# ProPrj_E24_5_0.net
KiCad netlist of a schematic drawn in EasyEDA Pro
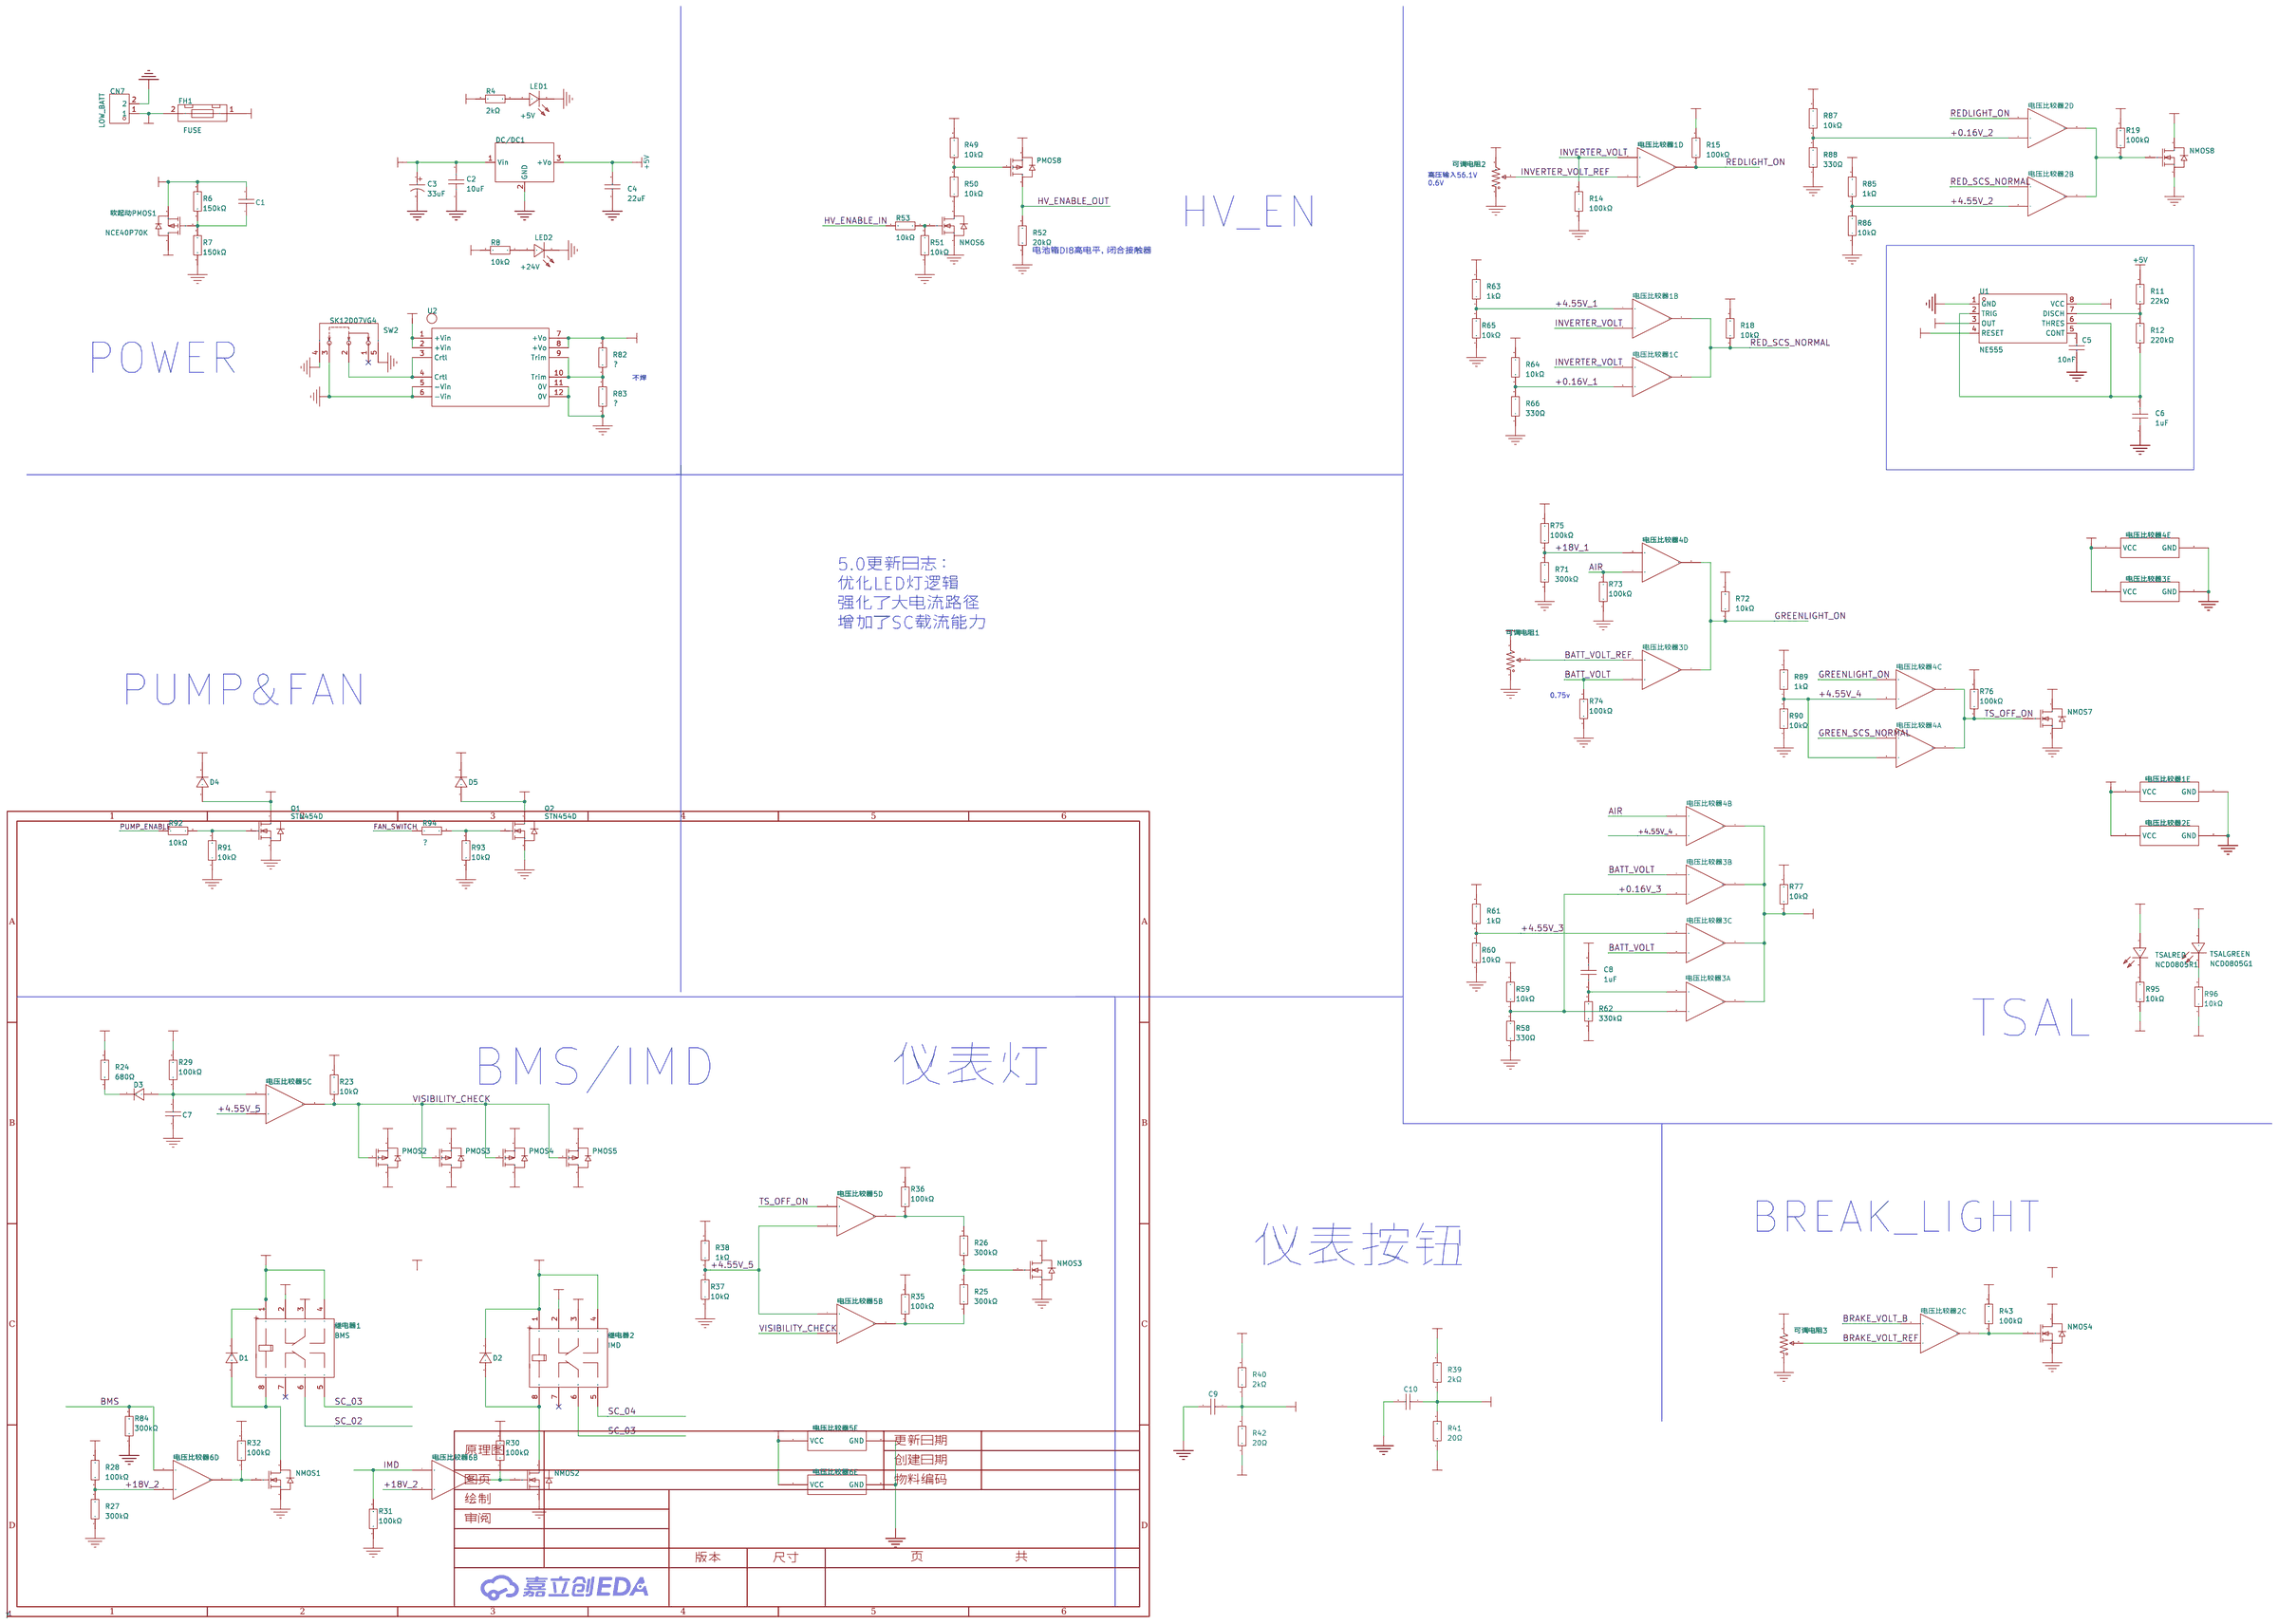
[diagram p0: P1]
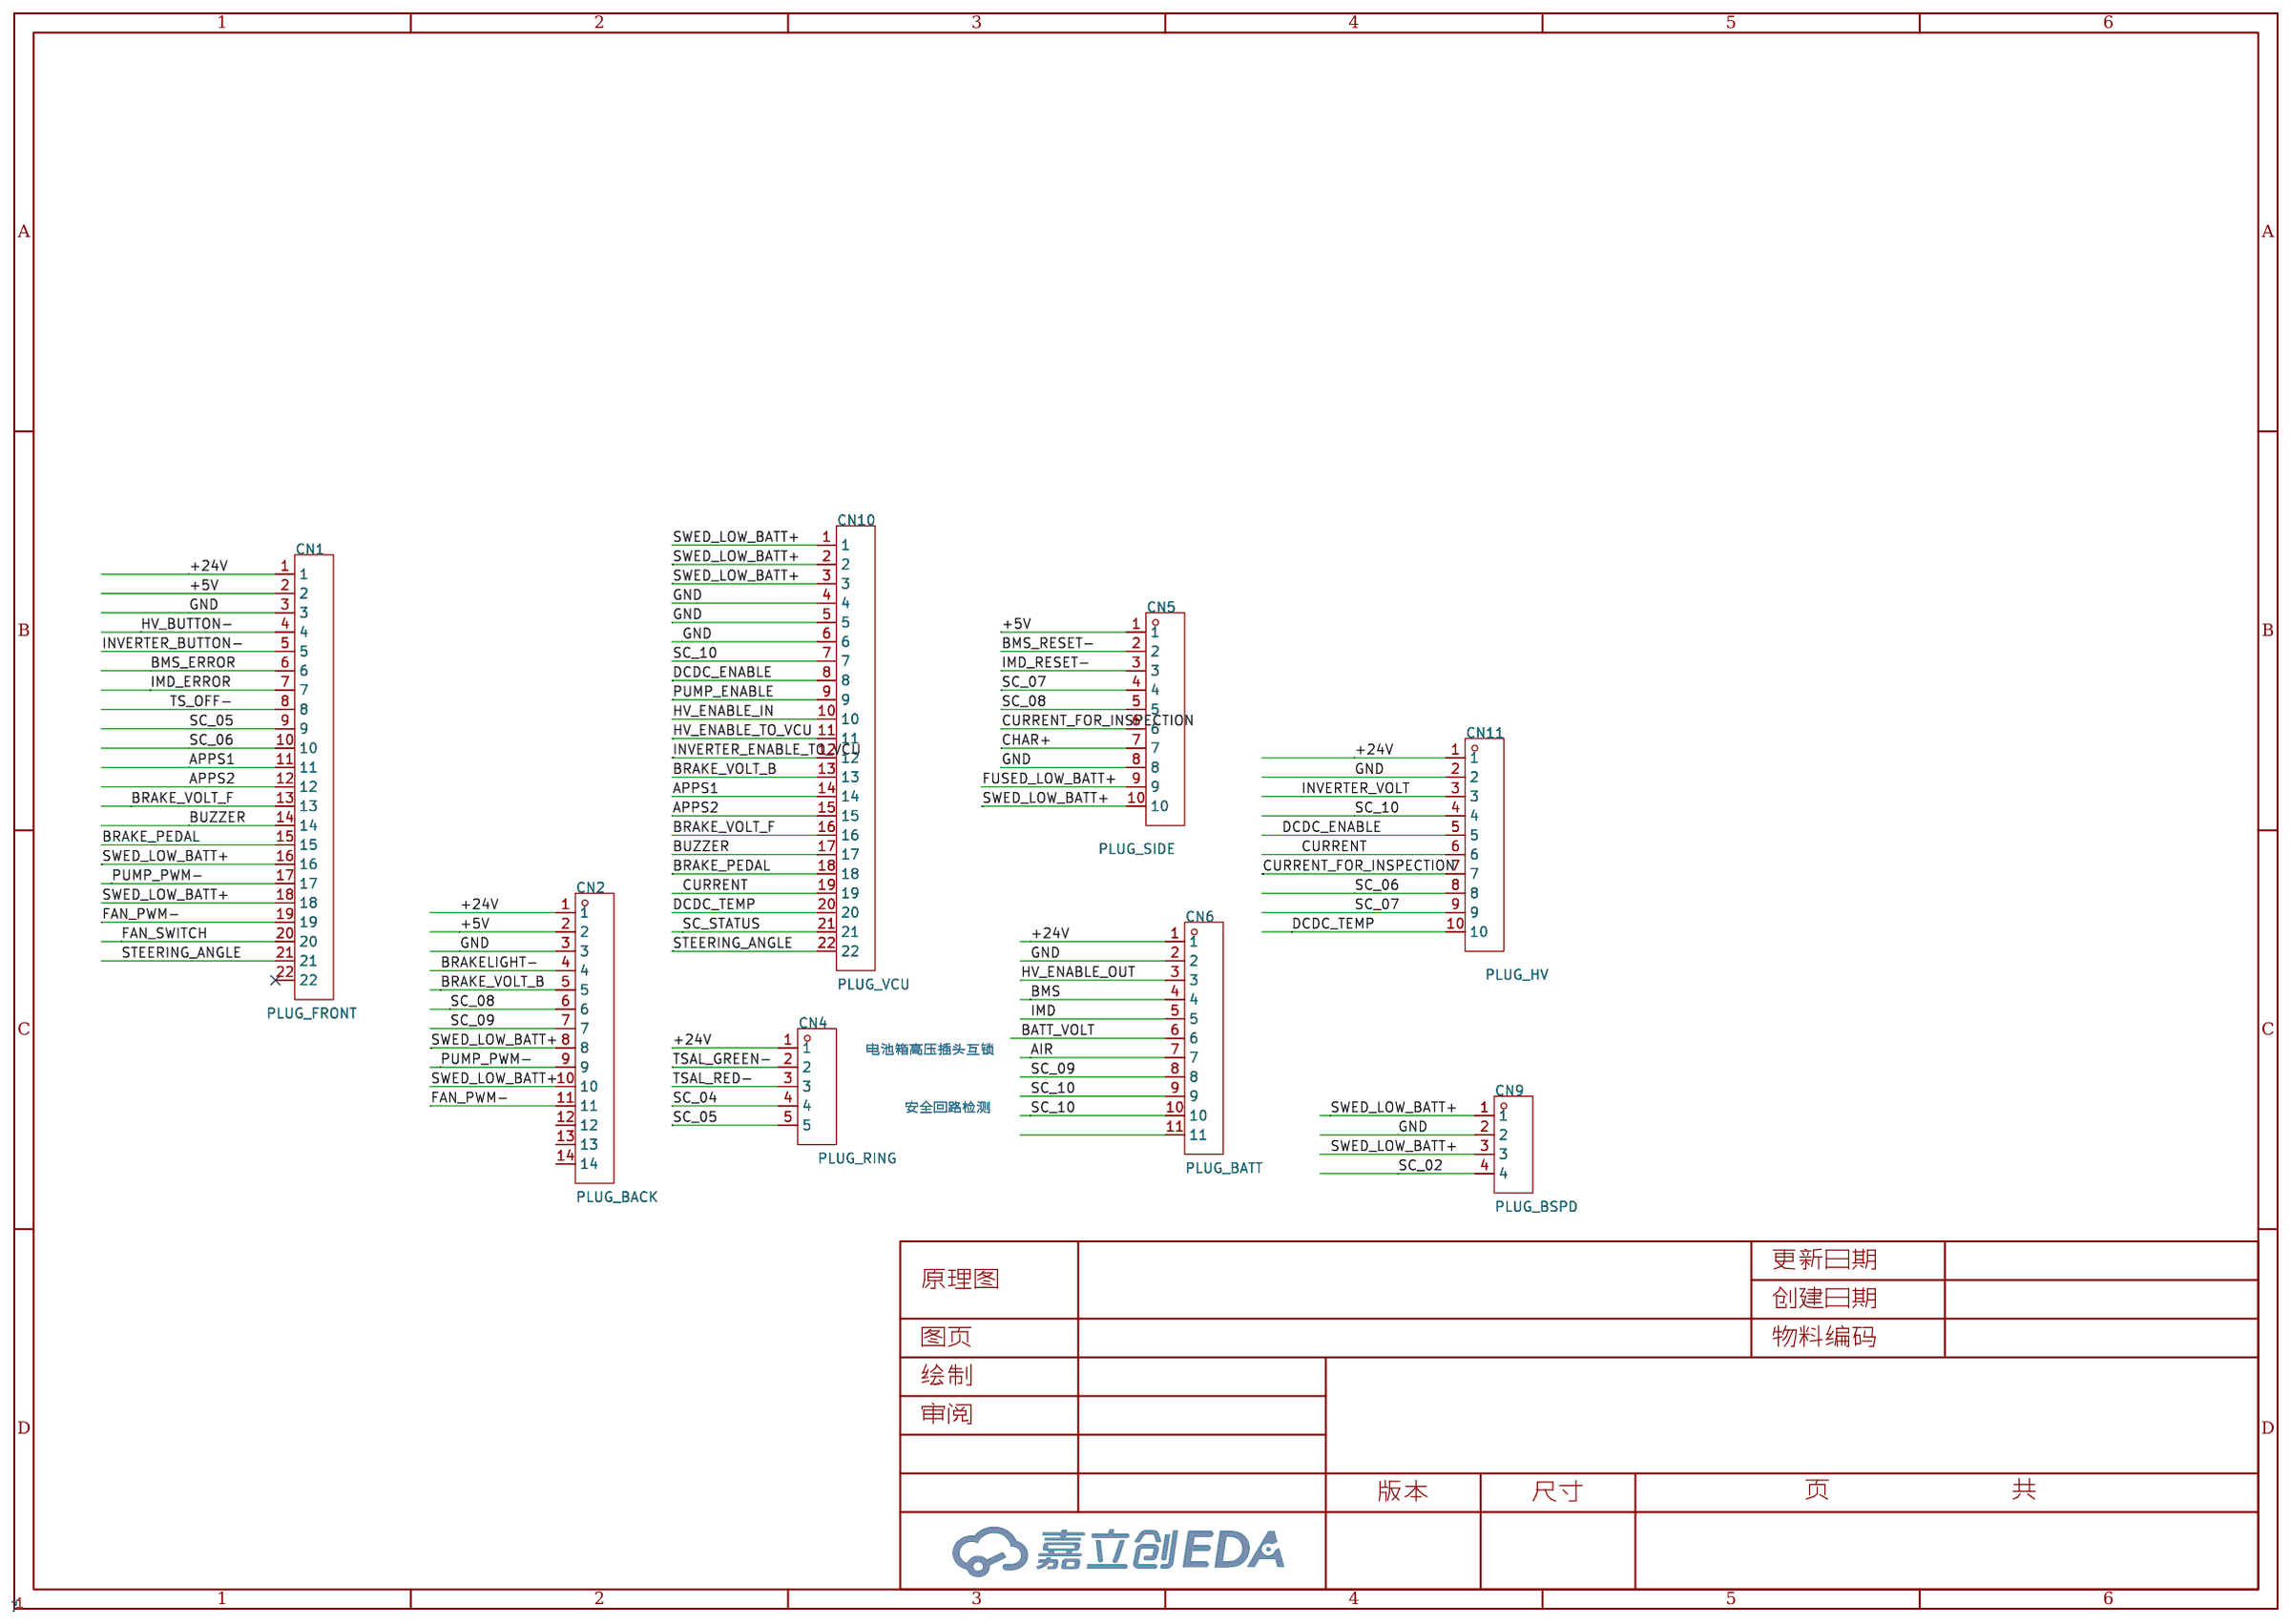
[diagram p1: P2]
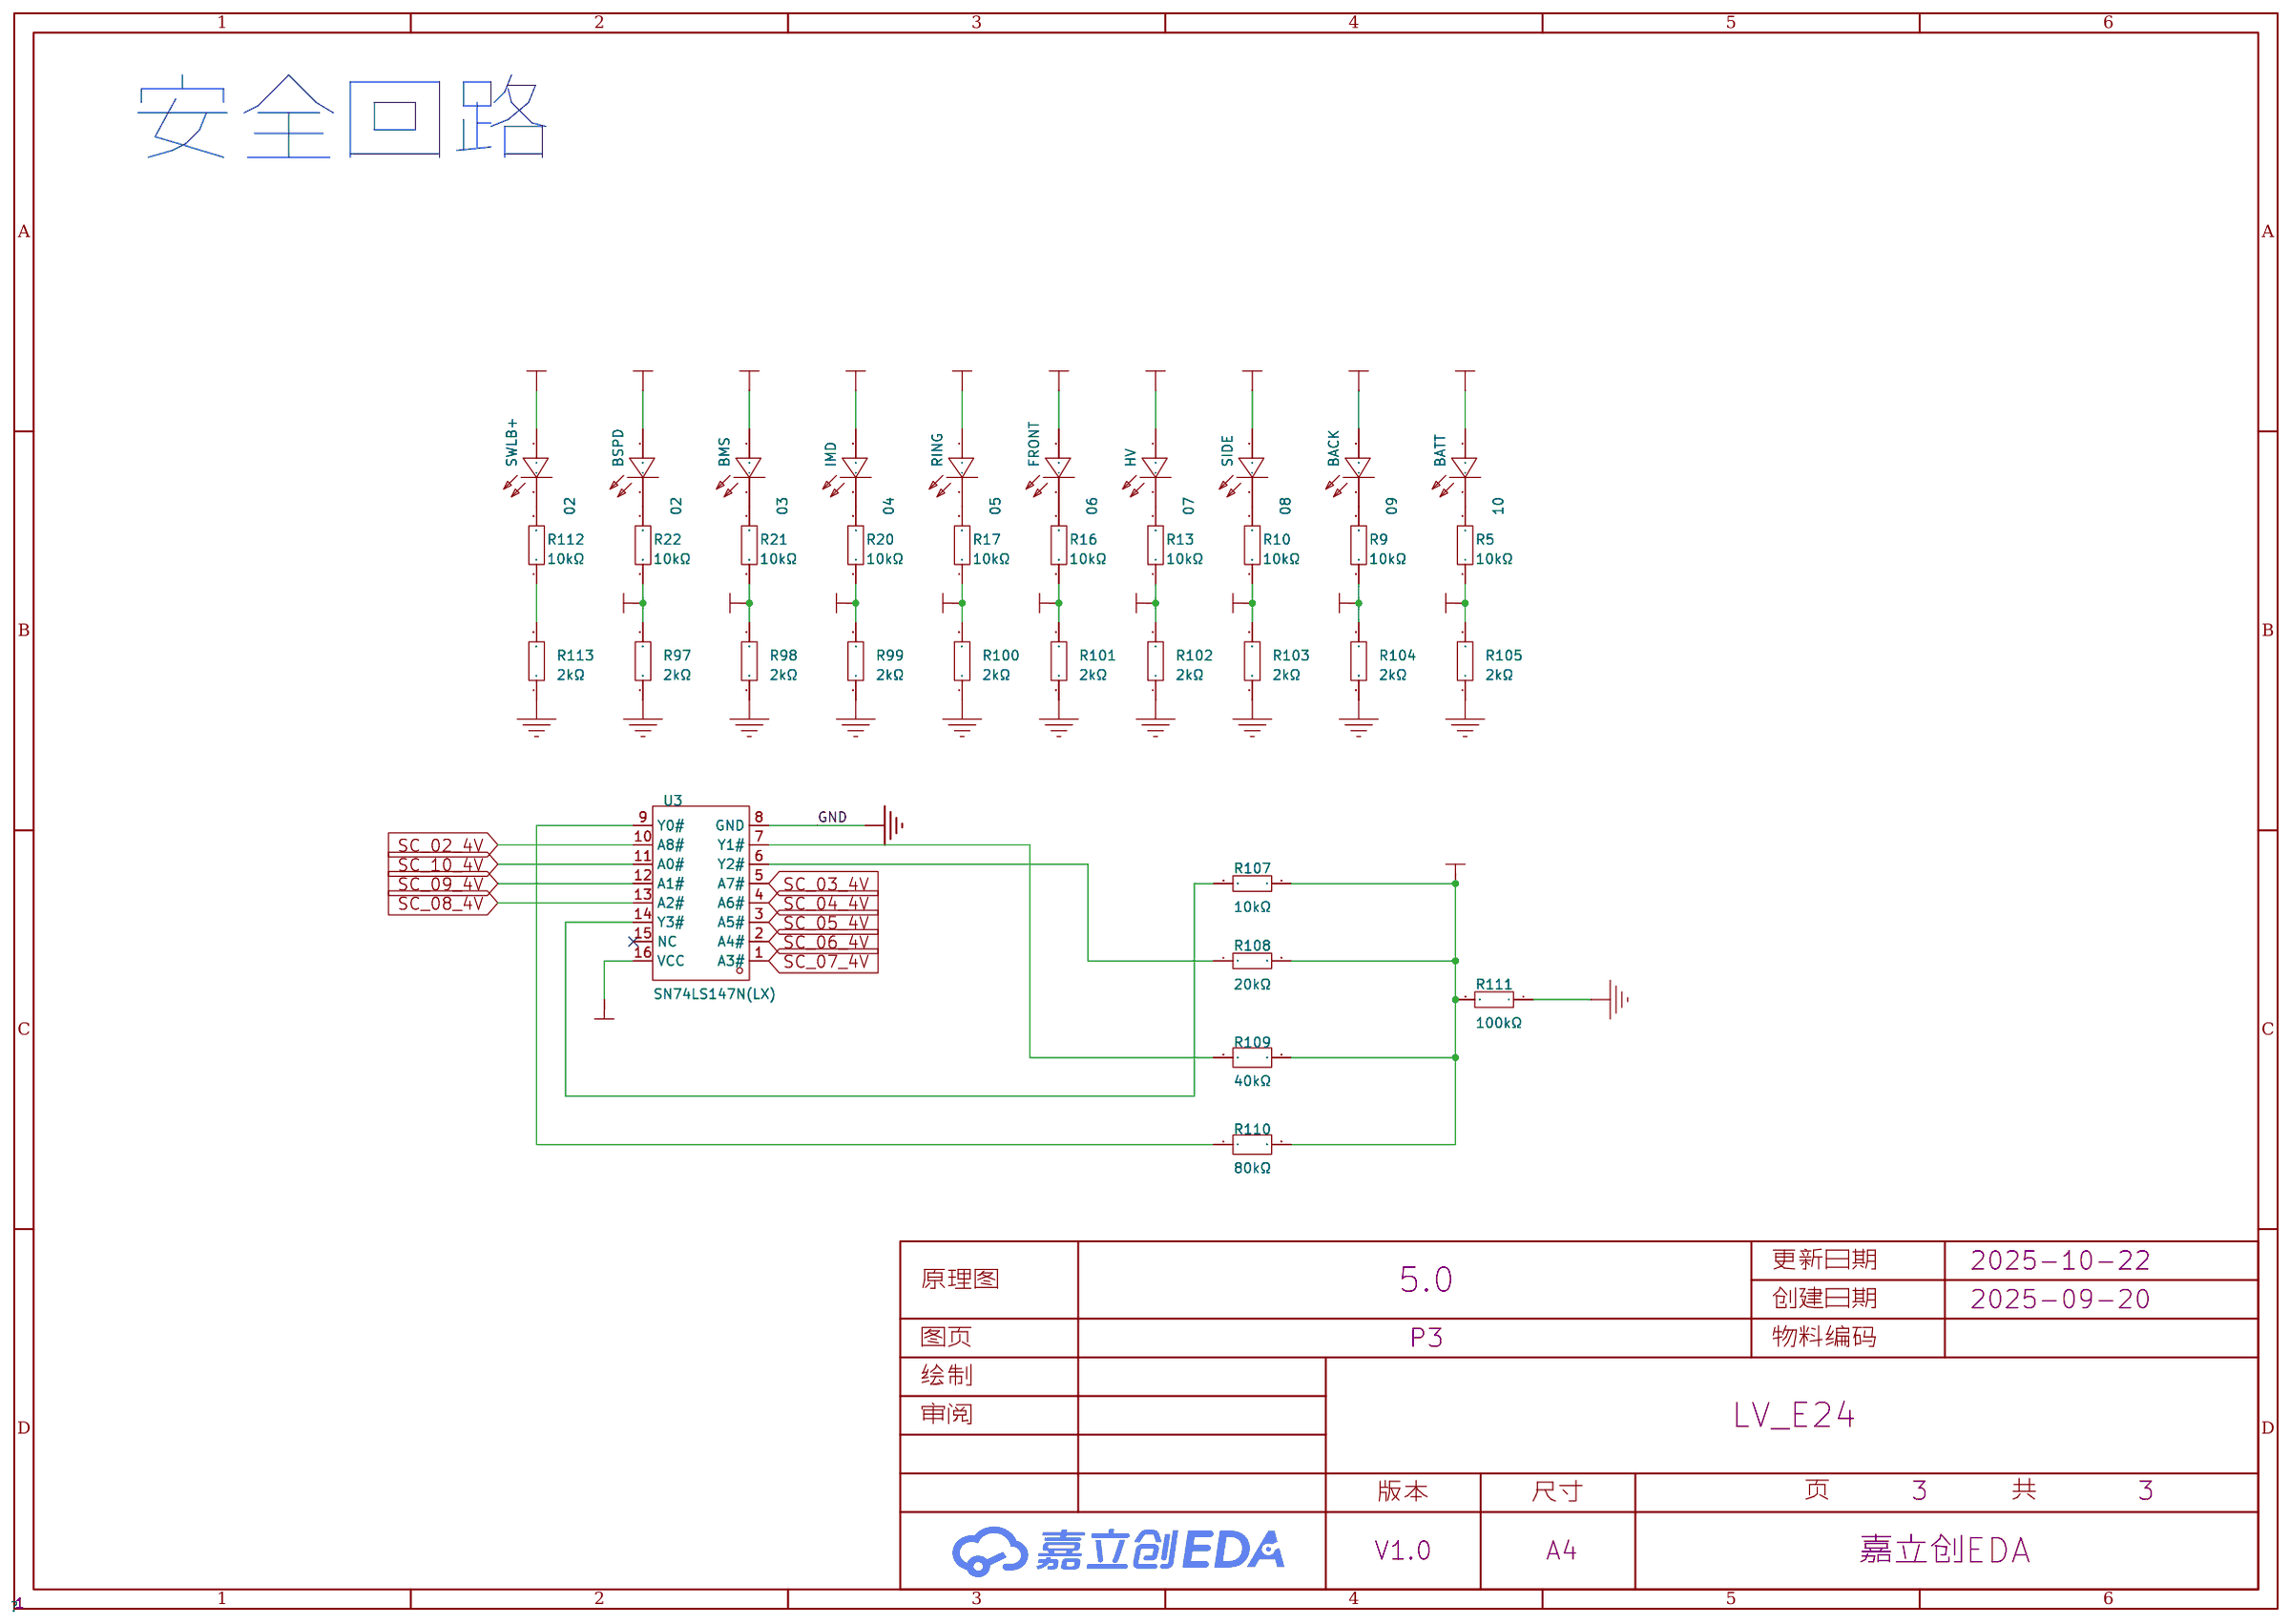
[diagram p2: P3]

(export (version "E")
  (design (tool "Eeschema 10.0.6"))
  (components
    (comp (ref "C1") (value "10uF") (libsource (lib "easyedapro") (part "C")))
    (comp (ref "C2")
      (value "10uF")
      (footprint "easyedapro:C1206")
      (description "容值:10uF;精度:±10%;额定电压:50V;材质(温度系数):X5R;")
      (fields
        (field (name "Manufacturer Part") "CS3216X5R106K500NRI")
        (field (name "Manufacturer") "SAMWHA(三和)")
      )
      (libsource (lib "easyedapro") (part "CS3216X5R106K500NRI"))
    )
    (comp (ref "C3")
      (value "33uF")
      (footprint "easyedapro:CAP-SMD_BD6.3-L6.6-W6.6-FD")
      (description "容值:33uF;精度:±20%;额定电压:35V;纹波电流:41mA@120Hz;等效串联电阻:-;")
      (fields (field (name "Manufacturer Part") "RVT1V330M0605") (field (name "Manufacturer") "ROQANG(容强)"))
      (libsource (lib "easyedapro") (part "RVT1V330M0605"))
    )
    (comp (ref "C4")
      (value "22uF")
      (footprint "easyedapro:C0805")
      (description "容值:22uF;精度:±20%;额定电压:10V;材质(温度系数):X5R;")
      (fields
        (field (name "Manufacturer Part") "CL21A226MPQNNNE")
        (field (name "Manufacturer") "SAMSUNG(三星)")
      )
      (libsource (lib "easyedapro") (part "CL21A226MPQNNNE"))
    )
    (comp (ref "C5")
      (value "10nF")
      (footprint "easyedapro:C0603")
      (description "容值:10nF;精度:±10%;额定电压:50V;材质(温度系数):X7R;")
      (fields
        (field (name "Manufacturer Part") "CC0603KRX7R9BB103")
        (field (name "Manufacturer") "YAGEO(国巨)")
      )
      (libsource (lib "easyedapro") (part "CC0603KRX7R9BB103"))
    )
    (comp (ref "C6")
      (value "1uF")
      (footprint "easyedapro:C0603")
      (description "容值:1uF;精度:±10%;额定电压:50V;材质(温度系数):X5R;")
      (fields
        (field (name "Manufacturer Part") "CL10A105KB8NNNC")
        (field (name "Manufacturer") "SAMSUNG(三星)")
      )
      (libsource (lib "easyedapro") (part "CL10A105KB8NNNC"))
    )
    (comp (ref "C7") (value "10uF") (libsource (lib "easyedapro") (part "C")))
    (comp (ref "C8")
      (value "1uF")
      (footprint "easyedapro:C0603")
      (description "容值:1uF;精度:±10%;额定电压:50V;材质(温度系数):X5R;")
      (fields
        (field (name "Manufacturer Part") "CL10A105KB8NNNC")
        (field (name "Manufacturer") "SAMSUNG(三星)")
      )
      (libsource (lib "easyedapro") (part "CL10A105KB8NNNC"))
    )
    (comp (ref "C9") (value "10uF") (libsource (lib "easyedapro") (part "C")))
    (comp (ref "C10") (value "10uF") (libsource (lib "easyedapro") (part "C")))
    (comp (ref "CN7")
      (value "LOW_BATT")
      (footprint "easyedapro:CONN-TH_2P-P3.81_DB2EVC-3.81-2P-BK")
      (fields
        (field (name "Manufacturer Part") "DB2EVC-3.81-2P-GN")
        (field (name "Manufacturer") "DORABO(地博电气)")
      )
      (libsource (lib "easyedapro") (part "DB2EVC-3.81-2P"))
    )
    (comp (ref "D1") (value "1N4148W") (libsource (lib "easyedapro") (part "1N4148W")))
    (comp (ref "D2") (value "1N4148W") (libsource (lib "easyedapro") (part "1N4148W")))
    (comp (ref "D3") (value "1N4148W") (libsource (lib "easyedapro") (part "1N4148W")))
    (comp (ref "D4") (value "SS54") (libsource (lib "easyedapro") (part "SS54")))
    (comp (ref "D5") (value "SS54") (libsource (lib "easyedapro") (part "SS54")))
    (comp (ref "DC/DC1") (value "K7805-2000R3") (libsource (lib "easyedapro") (part "K7805-2000R3")))
    (comp (ref "FH1")
      (value "FUSE")
      (footprint "easyedapro:FUSE-TH_XF-506P")
      (description "保险丝座类型:-;电路数:-;保险丝类型:-;")
      (fields (field (name "Manufacturer Part") "XF-506P") (field (name "Manufacturer") "XFCN(兴飞)"))
      (libsource (lib "easyedapro") (part "XF-506P"))
    )
    (comp (ref "LED1")
      (value "+5V")
      (footprint "easyedapro:LED0805-R-RD_BLUE")
      (fields (field (name "Manufacturer Part") "SZYY0805B") (field (name "Manufacturer") "yongyu(永裕光电)"))
      (libsource (lib "easyedapro") (part "SZYY0805B"))
    )
    (comp (ref "LED2")
      (value "+24V")
      (footprint "easyedapro:LED0805-R-RD_BLUE")
      (fields (field (name "Manufacturer Part") "SZYY0805B") (field (name "Manufacturer") "yongyu(永裕光电)"))
      (libsource (lib "easyedapro") (part "SZYY0805B"))
    )
    (comp (ref "NMOS1") (value "2N7002") (libsource (lib "easyedapro") (part "2N7002")))
    (comp (ref "NMOS2") (value "2N7002") (libsource (lib "easyedapro") (part "2N7002")))
    (comp (ref "NMOS3") (value "2N7002") (libsource (lib "easyedapro") (part "2N7002")))
    (comp (ref "NMOS4") (value "WST4040") (libsource (lib "easyedapro") (part "WST4040")))
    (comp (ref "NMOS6") (value "2N7002") (libsource (lib "easyedapro") (part "2N7002")))
    (comp (ref "NMOS7") (value "WST4040") (libsource (lib "easyedapro") (part "WST4040")))
    (comp (ref "NMOS8") (value "WST4040") (libsource (lib "easyedapro") (part "WST4040")))
    (comp (ref "PMOS2") (value "LBSS84LT1G") (libsource (lib "easyedapro") (part "LBSS84LT1G")))
    (comp (ref "PMOS3") (value "LBSS84LT1G") (libsource (lib "easyedapro") (part "LBSS84LT1G")))
    (comp (ref "PMOS4") (value "LBSS84LT1G") (libsource (lib "easyedapro") (part "LBSS84LT1G")))
    (comp (ref "PMOS5") (value "LBSS84LT1G") (libsource (lib "easyedapro") (part "LBSS84LT1G")))
    (comp (ref "PMOS8") (value "LBSS84LT1G") (libsource (lib "easyedapro") (part "LBSS84LT1G")))
    (comp (ref "Q1")
      (value "STN454D")
      (footprint "easyedapro:TO-252-2_L6.5-W6.1-P4.58-LS10.0-BR")
      (description "类型:1个N沟道;漏源电压(Vdss):40V;连续漏极电流(Id):10A;功率(Pd):50W;导通电阻(RDS(on)@Vgs,Id):-;阈值电压(Vgs(th)@Id):-;")
      (fields (field (name "Manufacturer") "STANSON(司坦森)"))
      (libsource (lib "easyedapro") (part "STN454D"))
    )
    (comp (ref "Q2")
      (value "STN454D")
      (footprint "easyedapro:TO-252-2_L6.5-W6.1-P4.58-LS10.0-BR")
      (description "类型:1个N沟道;漏源电压(Vdss):40V;连续漏极电流(Id):10A;功率(Pd):50W;导通电阻(RDS(on)@Vgs,Id):-;阈值电压(Vgs(th)@Id):-;")
      (fields (field (name "Manufacturer") "STANSON(司坦森)"))
      (libsource (lib "easyedapro") (part "STN454D"))
    )
    (comp (ref "R4")
      (value "2kΩ")
      (footprint "easyedapro:R0603")
      (description "电阻类型:厚膜电阻;阻值:2kΩ;精度:±1%;功率:100mW;最大工作电压:75V;温度系数:±100ppm/°C;")
      (fields
        (field (name "Manufacturer Part") "0603WAF2001T5E")
        (field (name "Manufacturer") "UNI-ROYAL(厚声)")
      )
      (libsource (lib "easyedapro") (part "0603WAF2001T5E"))
    )
    (comp (ref "R6")
      (value "150kΩ")
      (footprint "easyedapro:R0603")
      (description "电阻类型:厚膜电阻;阻值:150kΩ;精度:±1%;功率:100mW;最大工作电压:75V;温度系数:±100ppm/°C;")
      (fields
        (field (name "Manufacturer Part") "0603WAF1503T5E")
        (field (name "Manufacturer") "UNI-ROYAL(厚声)")
      )
      (libsource (lib "easyedapro") (part "0603WAF1503T5E"))
    )
    (comp (ref "R7")
      (value "150kΩ")
      (footprint "easyedapro:R0603")
      (description "电阻类型:厚膜电阻;阻值:150kΩ;精度:±1%;功率:100mW;最大工作电压:75V;温度系数:±100ppm/°C;")
      (fields
        (field (name "Manufacturer Part") "0603WAF1503T5E")
        (field (name "Manufacturer") "UNI-ROYAL(厚声)")
      )
      (libsource (lib "easyedapro") (part "0603WAF1503T5E"))
    )
    (comp (ref "R8")
      (value "10kΩ")
      (footprint "easyedapro:R0603")
      (description "电阻类型:厚膜电阻;阻值:10kΩ;精度:±1%;功率:100mW;最大工作电压:75V;温度系数:±100ppm/°C;")
      (fields
        (field (name "Manufacturer Part") "0603WAF1002T5E")
        (field (name "Manufacturer") "UNI-ROYAL(厚声)")
      )
      (libsource (lib "easyedapro") (part "0603WAF1002T5E"))
    )
    (comp (ref "R11")
      (value "22kΩ")
      (footprint "easyedapro:R0603")
      (description "电阻类型:厚膜电阻;阻值:22kΩ;精度:±1%;功率:100mW;最大工作电压:75V;温度系数:±100ppm/°C;")
      (fields
        (field (name "Manufacturer Part") "0603WAF2202T5E")
        (field (name "Manufacturer") "UNI-ROYAL(厚声)")
      )
      (libsource (lib "easyedapro") (part "0603WAF2202T5E"))
    )
    (comp (ref "R12")
      (value "220kΩ")
      (footprint "easyedapro:R0603")
      (description "电阻类型:厚膜电阻;阻值:220kΩ;精度:±1%;功率:100mW;最大工作电压:75V;温度系数:±100ppm/°C;")
      (fields
        (field (name "Manufacturer Part") "0603WAF2203T5E")
        (field (name "Manufacturer") "UNI-ROYAL(厚声)")
      )
      (libsource (lib "easyedapro") (part "0603WAF2203T5E"))
    )
    (comp (ref "R14")
      (value "100kΩ")
      (footprint "easyedapro:R0603")
      (description "电阻类型:厚膜电阻;阻值:100kΩ;精度:±1%;功率:100mW;最大工作电压:75V;温度系数:±100ppm/°C;")
      (fields
        (field (name "Manufacturer Part") "0603WAF1003T5E")
        (field (name "Manufacturer") "UNI-ROYAL(厚声)")
      )
      (libsource (lib "easyedapro") (part "0603WAF1003T5E"))
    )
    (comp (ref "R15")
      (value "100kΩ")
      (footprint "easyedapro:R0603")
      (description "电阻类型:厚膜电阻;阻值:100kΩ;精度:±1%;功率:100mW;最大工作电压:75V;温度系数:±100ppm/°C;")
      (fields
        (field (name "Manufacturer Part") "0603WAF1003T5E")
        (field (name "Manufacturer") "UNI-ROYAL(厚声)")
      )
      (libsource (lib "easyedapro") (part "0603WAF1003T5E"))
    )
    (comp (ref "R18")
      (value "10kΩ")
      (footprint "easyedapro:R0603")
      (description "电阻类型:厚膜电阻;阻值:10kΩ;精度:±1%;功率:100mW;最大工作电压:75V;温度系数:±100ppm/°C;")
      (fields
        (field (name "Manufacturer Part") "0603WAF1002T5E")
        (field (name "Manufacturer") "UNI-ROYAL(厚声)")
      )
      (libsource (lib "easyedapro") (part "0603WAF1002T5E"))
    )
    (comp (ref "R19")
      (value "100kΩ")
      (footprint "easyedapro:R0603")
      (description "电阻类型:厚膜电阻;阻值:100kΩ;精度:±1%;功率:100mW;最大工作电压:75V;温度系数:±100ppm/°C;")
      (fields
        (field (name "Manufacturer Part") "0603WAF1003T5E")
        (field (name "Manufacturer") "UNI-ROYAL(厚声)")
      )
      (libsource (lib "easyedapro") (part "0603WAF1003T5E"))
    )
    (comp (ref "R23")
      (value "10kΩ")
      (footprint "easyedapro:R0603")
      (description "电阻类型:厚膜电阻;阻值:10kΩ;精度:±1%;功率:100mW;最大工作电压:75V;温度系数:±100ppm/°C;")
      (fields
        (field (name "Manufacturer Part") "0603WAF1002T5E")
        (field (name "Manufacturer") "UNI-ROYAL(厚声)")
      )
      (libsource (lib "easyedapro") (part "0603WAF1002T5E"))
    )
    (comp (ref "R24")
      (value "680Ω")
      (footprint "easyedapro:R0603")
      (description "电阻类型:厚膜电阻;阻值:680Ω;精度:±1%;功率:100mW;最大工作电压:75V;温度系数:±100ppm/°C;")
      (fields
        (field (name "Manufacturer Part") "0603WAF6800T5E")
        (field (name "Manufacturer") "UNI-ROYAL(厚声)")
      )
      (libsource (lib "easyedapro") (part "0603WAF6800T5E"))
    )
    (comp (ref "R25")
      (value "300kΩ")
      (footprint "easyedapro:R0603")
      (description "电阻类型:厚膜电阻;阻值:300kΩ;精度:±1%;功率:100mW;最大工作电压:75V;温度系数:±100ppm/°C;")
      (fields
        (field (name "Manufacturer Part") "0603WAF3003T5E")
        (field (name "Manufacturer") "UNI-ROYAL(厚声)")
      )
      (libsource (lib "easyedapro") (part "0603WAF3003T5E"))
    )
    (comp (ref "R26")
      (value "300kΩ")
      (footprint "easyedapro:R0603")
      (description "电阻类型:厚膜电阻;阻值:300kΩ;精度:±1%;功率:100mW;最大工作电压:75V;温度系数:±100ppm/°C;")
      (fields
        (field (name "Manufacturer Part") "0603WAF3003T5E")
        (field (name "Manufacturer") "UNI-ROYAL(厚声)")
      )
      (libsource (lib "easyedapro") (part "0603WAF3003T5E"))
    )
    (comp (ref "R27")
      (value "300kΩ")
      (footprint "easyedapro:R0603")
      (description "电阻类型:厚膜电阻;阻值:300kΩ;精度:±1%;功率:100mW;最大工作电压:75V;温度系数:±100ppm/°C;")
      (fields
        (field (name "Manufacturer Part") "0603WAF3003T5E")
        (field (name "Manufacturer") "UNI-ROYAL(厚声)")
      )
      (libsource (lib "easyedapro") (part "0603WAF3003T5E"))
    )
    (comp (ref "R28")
      (value "100kΩ")
      (footprint "easyedapro:R0603")
      (description "电阻类型:厚膜电阻;阻值:100kΩ;精度:±1%;功率:100mW;最大工作电压:75V;温度系数:±100ppm/°C;")
      (fields
        (field (name "Manufacturer Part") "0603WAF1003T5E")
        (field (name "Manufacturer") "UNI-ROYAL(厚声)")
      )
      (libsource (lib "easyedapro") (part "0603WAF1003T5E"))
    )
    (comp (ref "R29")
      (value "100kΩ")
      (footprint "easyedapro:R0603")
      (description "电阻类型:厚膜电阻;阻值:100kΩ;精度:±1%;功率:100mW;最大工作电压:75V;温度系数:±100ppm/°C;")
      (fields
        (field (name "Manufacturer Part") "0603WAF1003T5E")
        (field (name "Manufacturer") "UNI-ROYAL(厚声)")
      )
      (libsource (lib "easyedapro") (part "0603WAF1003T5E"))
    )
    (comp (ref "R30")
      (value "100kΩ")
      (footprint "easyedapro:R0603")
      (description "电阻类型:厚膜电阻;阻值:100kΩ;精度:±1%;功率:100mW;最大工作电压:75V;温度系数:±100ppm/°C;")
      (fields
        (field (name "Manufacturer Part") "0603WAF1003T5E")
        (field (name "Manufacturer") "UNI-ROYAL(厚声)")
      )
      (libsource (lib "easyedapro") (part "0603WAF1003T5E"))
    )
    (comp (ref "R31")
      (value "100kΩ")
      (footprint "easyedapro:R0603")
      (description "电阻类型:厚膜电阻;阻值:100kΩ;精度:±1%;功率:100mW;最大工作电压:75V;温度系数:±100ppm/°C;")
      (fields
        (field (name "Manufacturer Part") "0603WAF1003T5E")
        (field (name "Manufacturer") "UNI-ROYAL(厚声)")
      )
      (libsource (lib "easyedapro") (part "0603WAF1003T5E"))
    )
    (comp (ref "R32")
      (value "100kΩ")
      (footprint "easyedapro:R0603")
      (description "电阻类型:厚膜电阻;阻值:100kΩ;精度:±1%;功率:100mW;最大工作电压:75V;温度系数:±100ppm/°C;")
      (fields
        (field (name "Manufacturer Part") "0603WAF1003T5E")
        (field (name "Manufacturer") "UNI-ROYAL(厚声)")
      )
      (libsource (lib "easyedapro") (part "0603WAF1003T5E"))
    )
    (comp (ref "R35")
      (value "100kΩ")
      (footprint "easyedapro:R0603")
      (description "电阻类型:厚膜电阻;阻值:100kΩ;精度:±1%;功率:100mW;最大工作电压:75V;温度系数:±100ppm/°C;")
      (fields
        (field (name "Manufacturer Part") "0603WAF1003T5E")
        (field (name "Manufacturer") "UNI-ROYAL(厚声)")
      )
      (libsource (lib "easyedapro") (part "0603WAF1003T5E"))
    )
    (comp (ref "R36")
      (value "100kΩ")
      (footprint "easyedapro:R0603")
      (description "电阻类型:厚膜电阻;阻值:100kΩ;精度:±1%;功率:100mW;最大工作电压:75V;温度系数:±100ppm/°C;")
      (fields
        (field (name "Manufacturer Part") "0603WAF1003T5E")
        (field (name "Manufacturer") "UNI-ROYAL(厚声)")
      )
      (libsource (lib "easyedapro") (part "0603WAF1003T5E"))
    )
    (comp (ref "R37")
      (value "10kΩ")
      (footprint "easyedapro:R0603")
      (description "电阻类型:厚膜电阻;阻值:10kΩ;精度:±1%;功率:100mW;最大工作电压:75V;温度系数:±100ppm/°C;")
      (fields
        (field (name "Manufacturer Part") "0603WAF1002T5E")
        (field (name "Manufacturer") "UNI-ROYAL(厚声)")
      )
      (libsource (lib "easyedapro") (part "0603WAF1002T5E"))
    )
    (comp (ref "R38")
      (value "1kΩ")
      (footprint "easyedapro:R0603")
      (description "电阻类型:厚膜电阻;阻值:1kΩ;精度:±1%;功率:100mW;最大工作电压:75V;温度系数:±100ppm/°C;")
      (fields
        (field (name "Manufacturer Part") "0603WAF1001T5E")
        (field (name "Manufacturer") "UNI-ROYAL(厚声)")
      )
      (libsource (lib "easyedapro") (part "0603WAF1001T5E"))
    )
    (comp (ref "R39")
      (value "2kΩ")
      (footprint "easyedapro:R0603")
      (description "电阻类型:厚膜电阻;阻值:2kΩ;精度:±1%;功率:100mW;最大工作电压:75V;温度系数:±100ppm/°C;")
      (fields
        (field (name "Manufacturer Part") "0603WAF2001T5E")
        (field (name "Manufacturer") "UNI-ROYAL(厚声)")
      )
      (libsource (lib "easyedapro") (part "0603WAF2001T5E"))
    )
    (comp (ref "R40")
      (value "2kΩ")
      (footprint "easyedapro:R0603")
      (description "电阻类型:厚膜电阻;阻值:2kΩ;精度:±1%;功率:100mW;最大工作电压:75V;温度系数:±100ppm/°C;")
      (fields
        (field (name "Manufacturer Part") "0603WAF2001T5E")
        (field (name "Manufacturer") "UNI-ROYAL(厚声)")
      )
      (libsource (lib "easyedapro") (part "0603WAF2001T5E"))
    )
    (comp (ref "R41")
      (value "20Ω")
      (footprint "easyedapro:R0603")
      (description "电阻类型:厚膜电阻;阻值:20Ω;精度:±1%;功率:100mW;最大工作电压:75V;温度系数:±100ppm/°C;")
      (fields
        (field (name "Manufacturer Part") "0603WAF200JT5E")
        (field (name "Manufacturer") "UNI-ROYAL(厚声)")
      )
      (libsource (lib "easyedapro") (part "0603WAF200JT5E"))
    )
    (comp (ref "R42")
      (value "20Ω")
      (footprint "easyedapro:R0603")
      (description "电阻类型:厚膜电阻;阻值:20Ω;精度:±1%;功率:100mW;最大工作电压:75V;温度系数:±100ppm/°C;")
      (fields
        (field (name "Manufacturer Part") "0603WAF200JT5E")
        (field (name "Manufacturer") "UNI-ROYAL(厚声)")
      )
      (libsource (lib "easyedapro") (part "0603WAF200JT5E"))
    )
    (comp (ref "R43")
      (value "100kΩ")
      (footprint "easyedapro:R0603")
      (description "电阻类型:厚膜电阻;阻值:100kΩ;精度:±1%;功率:100mW;最大工作电压:75V;温度系数:±100ppm/°C;")
      (fields
        (field (name "Manufacturer Part") "0603WAF1003T5E")
        (field (name "Manufacturer") "UNI-ROYAL(厚声)")
      )
      (libsource (lib "easyedapro") (part "0603WAF1003T5E"))
    )
    (comp (ref "R49")
      (value "10kΩ")
      (footprint "easyedapro:R0603")
      (description "电阻类型:厚膜电阻;阻值:10kΩ;精度:±1%;功率:100mW;最大工作电压:75V;温度系数:±100ppm/°C;")
      (fields
        (field (name "Manufacturer Part") "0603WAF1002T5E")
        (field (name "Manufacturer") "UNI-ROYAL(厚声)")
      )
      (libsource (lib "easyedapro") (part "0603WAF1002T5E"))
    )
    (comp (ref "R50")
      (value "10kΩ")
      (footprint "easyedapro:R0603")
      (description "电阻类型:厚膜电阻;阻值:10kΩ;精度:±1%;功率:100mW;最大工作电压:75V;温度系数:±100ppm/°C;")
      (fields
        (field (name "Manufacturer Part") "0603WAF1002T5E")
        (field (name "Manufacturer") "UNI-ROYAL(厚声)")
      )
      (libsource (lib "easyedapro") (part "0603WAF1002T5E"))
    )
    (comp (ref "R51")
      (value "10kΩ")
      (footprint "easyedapro:R0603")
      (description "电阻类型:厚膜电阻;阻值:10kΩ;精度:±1%;功率:100mW;最大工作电压:75V;温度系数:±100ppm/°C;")
      (fields
        (field (name "Manufacturer Part") "0603WAF1002T5E")
        (field (name "Manufacturer") "UNI-ROYAL(厚声)")
      )
      (libsource (lib "easyedapro") (part "0603WAF1002T5E"))
    )
    (comp (ref "R52")
      (value "20kΩ")
      (footprint "easyedapro:R0603")
      (description "电阻类型:厚膜电阻;阻值:20kΩ;精度:±1%;功率:100mW;最大工作电压:75V;温度系数:±100ppm/°C;")
      (fields
        (field (name "Manufacturer Part") "0603WAF2002T5E")
        (field (name "Manufacturer") "UNI-ROYAL(厚声)")
      )
      (libsource (lib "easyedapro") (part "0603WAF2002T5E"))
    )
    (comp (ref "R53")
      (value "10kΩ")
      (footprint "easyedapro:R0603")
      (description "电阻类型:厚膜电阻;阻值:10kΩ;精度:±1%;功率:100mW;最大工作电压:75V;温度系数:±100ppm/°C;")
      (fields
        (field (name "Manufacturer Part") "0603WAF1002T5E")
        (field (name "Manufacturer") "UNI-ROYAL(厚声)")
      )
      (libsource (lib "easyedapro") (part "0603WAF1002T5E"))
    )
    (comp (ref "R58")
      (value "330Ω")
      (footprint "easyedapro:R0603")
      (description "电阻类型:厚膜电阻;阻值:330Ω;精度:±1%;功率:100mW;最大工作电压:75V;温度系数:±100ppm/°C;")
      (fields
        (field (name "Manufacturer Part") "0603WAF3300T5E")
        (field (name "Manufacturer") "UNI-ROYAL(厚声)")
      )
      (libsource (lib "easyedapro") (part "0603WAF3300T5E"))
    )
    (comp (ref "R59")
      (value "10kΩ")
      (footprint "easyedapro:R0603")
      (description "电阻类型:厚膜电阻;阻值:10kΩ;精度:±1%;功率:100mW;最大工作电压:75V;温度系数:±100ppm/°C;")
      (fields
        (field (name "Manufacturer Part") "0603WAF1002T5E")
        (field (name "Manufacturer") "UNI-ROYAL(厚声)")
      )
      (libsource (lib "easyedapro") (part "0603WAF1002T5E"))
    )
    (comp (ref "R60")
      (value "10kΩ")
      (footprint "easyedapro:R0603")
      (description "电阻类型:厚膜电阻;阻值:10kΩ;精度:±1%;功率:100mW;最大工作电压:75V;温度系数:±100ppm/°C;")
      (fields
        (field (name "Manufacturer Part") "0603WAF1002T5E")
        (field (name "Manufacturer") "UNI-ROYAL(厚声)")
      )
      (libsource (lib "easyedapro") (part "0603WAF1002T5E"))
    )
    (comp (ref "R61")
      (value "1kΩ")
      (footprint "easyedapro:R0603")
      (description "电阻类型:厚膜电阻;阻值:1kΩ;精度:±1%;功率:100mW;最大工作电压:75V;温度系数:±100ppm/°C;")
      (fields
        (field (name "Manufacturer Part") "0603WAF1001T5E")
        (field (name "Manufacturer") "UNI-ROYAL(厚声)")
      )
      (libsource (lib "easyedapro") (part "0603WAF1001T5E"))
    )
    (comp (ref "R62")
      (value "330kΩ")
      (footprint "easyedapro:R0603")
      (description "电阻类型:厚膜电阻;阻值:330kΩ;精度:±1%;功率:100mW;最大工作电压:75V;温度系数:±100ppm/°C;")
      (fields
        (field (name "Manufacturer Part") "0603WAF3303T5E")
        (field (name "Manufacturer") "UNI-ROYAL(厚声)")
      )
      (libsource (lib "easyedapro") (part "0603WAF3303T5E"))
    )
    (comp (ref "R63")
      (value "1kΩ")
      (footprint "easyedapro:R0603")
      (description "电阻类型:厚膜电阻;阻值:1kΩ;精度:±1%;功率:100mW;最大工作电压:75V;温度系数:±100ppm/°C;")
      (fields
        (field (name "Manufacturer Part") "0603WAF1001T5E")
        (field (name "Manufacturer") "UNI-ROYAL(厚声)")
      )
      (libsource (lib "easyedapro") (part "0603WAF1001T5E"))
    )
    (comp (ref "R64")
      (value "10kΩ")
      (footprint "easyedapro:R0603")
      (description "电阻类型:厚膜电阻;阻值:10kΩ;精度:±1%;功率:100mW;最大工作电压:75V;温度系数:±100ppm/°C;")
      (fields
        (field (name "Manufacturer Part") "0603WAF1002T5E")
        (field (name "Manufacturer") "UNI-ROYAL(厚声)")
      )
      (libsource (lib "easyedapro") (part "0603WAF1002T5E"))
    )
    (comp (ref "R65")
      (value "10kΩ")
      (footprint "easyedapro:R0603")
      (description "电阻类型:厚膜电阻;阻值:10kΩ;精度:±1%;功率:100mW;最大工作电压:75V;温度系数:±100ppm/°C;")
      (fields
        (field (name "Manufacturer Part") "0603WAF1002T5E")
        (field (name "Manufacturer") "UNI-ROYAL(厚声)")
      )
      (libsource (lib "easyedapro") (part "0603WAF1002T5E"))
    )
    (comp (ref "R66")
      (value "330Ω")
      (footprint "easyedapro:R0603")
      (description "电阻类型:厚膜电阻;阻值:330Ω;精度:±1%;功率:100mW;最大工作电压:75V;温度系数:±100ppm/°C;")
      (fields
        (field (name "Manufacturer Part") "0603WAF3300T5E")
        (field (name "Manufacturer") "UNI-ROYAL(厚声)")
      )
      (libsource (lib "easyedapro") (part "0603WAF3300T5E"))
    )
    (comp (ref "R71")
      (value "300kΩ")
      (footprint "easyedapro:R0603")
      (description "电阻类型:厚膜电阻;阻值:300kΩ;精度:±1%;功率:100mW;最大工作电压:75V;温度系数:±100ppm/°C;")
      (fields
        (field (name "Manufacturer Part") "0603WAF3003T5E")
        (field (name "Manufacturer") "UNI-ROYAL(厚声)")
      )
      (libsource (lib "easyedapro") (part "0603WAF3003T5E"))
    )
    (comp (ref "R72")
      (value "10kΩ")
      (footprint "easyedapro:R0603")
      (description "电阻类型:厚膜电阻;阻值:10kΩ;精度:±1%;功率:100mW;最大工作电压:75V;温度系数:±100ppm/°C;")
      (fields
        (field (name "Manufacturer Part") "0603WAF1002T5E")
        (field (name "Manufacturer") "UNI-ROYAL(厚声)")
      )
      (libsource (lib "easyedapro") (part "0603WAF1002T5E"))
    )
    (comp (ref "R73")
      (value "100kΩ")
      (footprint "easyedapro:R0603")
      (description "电阻类型:厚膜电阻;阻值:100kΩ;精度:±1%;功率:100mW;最大工作电压:75V;温度系数:±100ppm/°C;")
      (fields
        (field (name "Manufacturer Part") "0603WAF1003T5E")
        (field (name "Manufacturer") "UNI-ROYAL(厚声)")
      )
      (libsource (lib "easyedapro") (part "0603WAF1003T5E"))
    )
    (comp (ref "R74")
      (value "100kΩ")
      (footprint "easyedapro:R0603")
      (description "电阻类型:厚膜电阻;阻值:100kΩ;精度:±1%;功率:100mW;最大工作电压:75V;温度系数:±100ppm/°C;")
      (fields
        (field (name "Manufacturer Part") "0603WAF1003T5E")
        (field (name "Manufacturer") "UNI-ROYAL(厚声)")
      )
      (libsource (lib "easyedapro") (part "0603WAF1003T5E"))
    )
    (comp (ref "R75")
      (value "100kΩ")
      (footprint "easyedapro:R0603")
      (description "电阻类型:厚膜电阻;阻值:100kΩ;精度:±1%;功率:100mW;最大工作电压:75V;温度系数:±100ppm/°C;")
      (fields
        (field (name "Manufacturer Part") "0603WAF1003T5E")
        (field (name "Manufacturer") "UNI-ROYAL(厚声)")
      )
      (libsource (lib "easyedapro") (part "0603WAF1003T5E"))
    )
    (comp (ref "R76")
      (value "100kΩ")
      (footprint "easyedapro:R0603")
      (description "电阻类型:厚膜电阻;阻值:100kΩ;精度:±1%;功率:100mW;最大工作电压:75V;温度系数:±100ppm/°C;")
      (fields
        (field (name "Manufacturer Part") "0603WAF1003T5E")
        (field (name "Manufacturer") "UNI-ROYAL(厚声)")
      )
      (libsource (lib "easyedapro") (part "0603WAF1003T5E"))
    )
    (comp (ref "R77")
      (value "10kΩ")
      (footprint "easyedapro:R0603")
      (description "电阻类型:厚膜电阻;阻值:10kΩ;精度:±1%;功率:100mW;最大工作电压:75V;温度系数:±100ppm/°C;")
      (fields
        (field (name "Manufacturer Part") "0603WAF1002T5E")
        (field (name "Manufacturer") "UNI-ROYAL(厚声)")
      )
      (libsource (lib "easyedapro") (part "0603WAF1002T5E"))
    )
    (comp (ref "R82")
      (value "？")
      (footprint "easyedapro:R0603")
      (description "电阻类型:厚膜电阻;阻值:10kΩ;精度:±1%;功率:100mW;最大工作电压:75V;温度系数:±100ppm/°C;")
      (fields
        (field (name "Manufacturer Part") "0603WAF1002T5E")
        (field (name "Manufacturer") "UNI-ROYAL(厚声)")
      )
      (libsource (lib "easyedapro") (part "0603WAF1002T5E"))
    )
    (comp (ref "R83")
      (value "？")
      (footprint "easyedapro:R0603")
      (description "电阻类型:厚膜电阻;阻值:10kΩ;精度:±1%;功率:100mW;最大工作电压:75V;温度系数:±100ppm/°C;")
      (fields
        (field (name "Manufacturer Part") "0603WAF1002T5E")
        (field (name "Manufacturer") "UNI-ROYAL(厚声)")
      )
      (libsource (lib "easyedapro") (part "0603WAF1002T5E"))
    )
    (comp (ref "R84")
      (value "300kΩ")
      (footprint "easyedapro:R0603")
      (description "电阻类型:厚膜电阻;阻值:100kΩ;精度:±1%;功率:100mW;最大工作电压:75V;温度系数:±100ppm/°C;")
      (fields
        (field (name "Manufacturer Part") "0603WAF3003T5E")
        (field (name "Manufacturer") "UNI-ROYAL(厚声)")
      )
      (libsource (lib "easyedapro") (part "0603WAF1003T5E"))
    )
    (comp (ref "R85")
      (value "1kΩ")
      (footprint "easyedapro:R0603")
      (description "电阻类型:厚膜电阻;阻值:1kΩ;精度:±1%;功率:100mW;最大工作电压:75V;温度系数:±100ppm/°C;")
      (fields
        (field (name "Manufacturer Part") "0603WAF1001T5E")
        (field (name "Manufacturer") "UNI-ROYAL(厚声)")
      )
      (libsource (lib "easyedapro") (part "0603WAF1001T5E"))
    )
    (comp (ref "R86")
      (value "10kΩ")
      (footprint "easyedapro:R0603")
      (description "电阻类型:厚膜电阻;阻值:10kΩ;精度:±1%;功率:100mW;最大工作电压:75V;温度系数:±100ppm/°C;")
      (fields
        (field (name "Manufacturer Part") "0603WAF1002T5E")
        (field (name "Manufacturer") "UNI-ROYAL(厚声)")
      )
      (libsource (lib "easyedapro") (part "0603WAF1002T5E"))
    )
    (comp (ref "R87")
      (value "10kΩ")
      (footprint "easyedapro:R0603")
      (description "电阻类型:厚膜电阻;阻值:10kΩ;精度:±1%;功率:100mW;最大工作电压:75V;温度系数:±100ppm/°C;")
      (fields
        (field (name "Manufacturer Part") "0603WAF1002T5E")
        (field (name "Manufacturer") "UNI-ROYAL(厚声)")
      )
      (libsource (lib "easyedapro") (part "0603WAF1002T5E"))
    )
    (comp (ref "R88")
      (value "330Ω")
      (footprint "easyedapro:R0603")
      (description "电阻类型:厚膜电阻;阻值:330Ω;精度:±1%;功率:100mW;最大工作电压:75V;温度系数:±100ppm/°C;")
      (fields
        (field (name "Manufacturer Part") "0603WAF3300T5E")
        (field (name "Manufacturer") "UNI-ROYAL(厚声)")
      )
      (libsource (lib "easyedapro") (part "0603WAF3300T5E"))
    )
    (comp (ref "R89")
      (value "1kΩ")
      (footprint "easyedapro:R0603")
      (description "电阻类型:厚膜电阻;阻值:1kΩ;精度:±1%;功率:100mW;最大工作电压:75V;温度系数:±100ppm/°C;")
      (fields
        (field (name "Manufacturer Part") "0603WAF1001T5E")
        (field (name "Manufacturer") "UNI-ROYAL(厚声)")
      )
      (libsource (lib "easyedapro") (part "0603WAF1001T5E"))
    )
    (comp (ref "R90")
      (value "10kΩ")
      (footprint "easyedapro:R0603")
      (description "电阻类型:厚膜电阻;阻值:10kΩ;精度:±1%;功率:100mW;最大工作电压:75V;温度系数:±100ppm/°C;")
      (fields
        (field (name "Manufacturer Part") "0603WAF1002T5E")
        (field (name "Manufacturer") "UNI-ROYAL(厚声)")
      )
      (libsource (lib "easyedapro") (part "0603WAF1002T5E"))
    )
    (comp (ref "R91")
      (value "10kΩ")
      (footprint "easyedapro:R0603")
      (description "电阻类型:厚膜电阻;阻值:10kΩ;精度:±1%;功率:100mW;最大工作电压:75V;温度系数:±100ppm/°C;")
      (fields
        (field (name "Manufacturer Part") "0603WAF1002T5E")
        (field (name "Manufacturer") "UNI-ROYAL(厚声)")
      )
      (libsource (lib "easyedapro") (part "0603WAF1002T5E"))
    )
    (comp (ref "R92")
      (value "10kΩ")
      (footprint "easyedapro:R0603")
      (description "电阻类型:厚膜电阻;阻值:10kΩ;精度:±1%;功率:100mW;最大工作电压:75V;温度系数:±100ppm/°C;")
      (fields
        (field (name "Manufacturer Part") "0603WAF1002T5E")
        (field (name "Manufacturer") "UNI-ROYAL(厚声)")
      )
      (libsource (lib "easyedapro") (part "0603WAF1002T5E"))
    )
    (comp (ref "R93")
      (value "10kΩ")
      (footprint "easyedapro:R0603")
      (description "电阻类型:厚膜电阻;阻值:10kΩ;精度:±1%;功率:100mW;最大工作电压:75V;温度系数:±100ppm/°C;")
      (fields
        (field (name "Manufacturer Part") "0603WAF1002T5E")
        (field (name "Manufacturer") "UNI-ROYAL(厚声)")
      )
      (libsource (lib "easyedapro") (part "0603WAF1002T5E"))
    )
    (comp (ref "R94")
      (value "？")
      (footprint "easyedapro:R0603")
      (description "电阻类型:厚膜电阻;阻值:10kΩ;精度:±1%;功率:100mW;最大工作电压:75V;温度系数:±100ppm/°C;")
      (fields
        (field (name "Manufacturer Part") "0603WAF1002T5E")
        (field (name "Manufacturer") "UNI-ROYAL(厚声)")
      )
      (libsource (lib "easyedapro") (part "0603WAF1002T5E"))
    )
    (comp (ref "R95")
      (value "10kΩ")
      (footprint "easyedapro:R0603")
      (description "电阻类型:厚膜电阻;阻值:10kΩ;精度:±1%;功率:100mW;最大工作电压:75V;温度系数:±100ppm/°C;")
      (fields
        (field (name "Manufacturer Part") "0603WAF1002T5E")
        (field (name "Manufacturer") "UNI-ROYAL(厚声)")
      )
      (libsource (lib "easyedapro") (part "0603WAF1002T5E"))
    )
    (comp (ref "R96")
      (value "10kΩ")
      (footprint "easyedapro:R0603")
      (description "电阻类型:厚膜电阻;阻值:10kΩ;精度:±1%;功率:100mW;最大工作电压:75V;温度系数:±100ppm/°C;")
      (fields
        (field (name "Manufacturer Part") "0603WAF1002T5E")
        (field (name "Manufacturer") "UNI-ROYAL(厚声)")
      )
      (libsource (lib "easyedapro") (part "0603WAF1002T5E"))
    )
    (comp (ref "SW2")
      (value "SK12D07VG4")
      (footprint "easyedapro:SW-TH_SK12D07VG4")
      (description "电路结构:单刀双掷;安装方式:-;额定电流(DC):500mA;额定电压(DC):50V;额定电流(AC):-;额定电压(AC):-;机械寿命:5千次;")
      (fields (field (name "Manufacturer") "SHOU HAN(首韩)"))
      (libsource (lib "easyedapro") (part "SK12D07VG4"))
    )
    (comp (ref "TSALGREEN")
      (value "NCD0805G1")
      (footprint "easyedapro:LED0805-R-RD")
      (fields (field (name "Manufacturer") "国星光电"))
      (libsource (lib "easyedapro") (part "FC-2012UGK-520D5"))
    )
    (comp (ref "TSALRED")
      (value "NCD0805R1")
      (footprint "easyedapro:LED0805-R-RD")
      (fields (field (name "Manufacturer") "国星光电"))
      (libsource (lib "easyedapro") (part "FC-2012HRK-620D"))
    )
    (comp (ref "U1")
      (value "NE555")
      (footprint "easyedapro:SOIC-8_L4.9-W3.9-P1.27-LS6.0-BL")
      (description "频率:-;是否可编程:-;重置时间:-;")
      (fields (field (name "Manufacturer") "IDCHIP(英锐芯)"))
      (libsource (lib "easyedapro") (part "NE555_C5125085"))
    )
    (comp (ref "U2")
      (value "~")
      (footprint "easyedapro:DCDC_b_package")
      (libsource (lib "easyedapro") (part "DCDC_b"))
    )
    (comp (ref "可调电阻1") (value "10kΩ") (libsource (lib "easyedapro") (part "3296W-1-103")))
    (comp (ref "可调电阻2") (value "10kΩ") (libsource (lib "easyedapro") (part "3296W-1-103")))
    (comp (ref "可调电阻3") (value "10kΩ") (libsource (lib "easyedapro") (part "3296W-1-103")))
    (comp (ref "电压比较器1") (value "LM339PT") (libsource (lib "easyedapro") (part "LM339PT")))
    (comp (ref "电压比较器2") (value "LM339PT") (libsource (lib "easyedapro") (part "LM339PT")))
    (comp (ref "电压比较器3") (value "LM339PT") (libsource (lib "easyedapro") (part "LM339PT")))
    (comp (ref "电压比较器4") (value "LM339PT") (libsource (lib "easyedapro") (part "LM339PT")))
    (comp (ref "电压比较器5") (value "LM339PT") (libsource (lib "easyedapro") (part "LM339PT")))
    (comp (ref "电压比较器6") (value "LM339PT") (libsource (lib "easyedapro") (part "LM339PT")))
    (comp (ref "继电器1") (value "BMS") (libsource (lib "easyedapro") (part "HFD4/5")))
    (comp (ref "继电器2") (value "IMD") (libsource (lib "easyedapro") (part "HFD4/5")))
    (comp (ref "软起动PMOS1")
      (value "NCE40P70K")
      (footprint "easyedapro:TO-252-2_L6.6-W6.1-P4.57-LS9.9-TL-CW")
      (fields (field (name "Manufacturer") "NCE(无锡新洁能)"))
      (libsource (lib "easyedapro") (part "NCE40P70K"))
    )
    (comp (ref "CN1")
      (value "PLUG_FRONT")
      (footprint "easyedapro:CONN-TH_22P-P3.81_DB2EVC-3.81-22P-GN")
      (fields
        (field (name "Manufacturer Part") "DB2EVC-3.81-22P-GN")
        (field (name "Manufacturer") "DORABO(地博电气)")
      )
      (libsource (lib "easyedapro") (part "DB2EVC-3.81-22P-GN"))
    )
    (comp (ref "CN2")
      (value "PLUG_BACK")
      (footprint "easyedapro:CONN-TH_14P-P3.81_DB2EVC-3.81-14P-GN")
      (fields
        (field (name "Manufacturer Part") "DB2EVC-3.81-14P-GN")
        (field (name "Manufacturer") "DORABO(地博电气)")
      )
      (libsource (lib "easyedapro") (part "DB2EVC-3.81-14P-GN"))
    )
    (comp (ref "CN4")
      (value "PLUG_RING")
      (footprint "easyedapro:CONN-TH_5P-P3.81_DB2EVC-3.81-5P")
      (fields (field (name "Manufacturer Part") "plug_ring") (field (name "Manufacturer") "DORABO(地博电气)"))
      (libsource (lib "easyedapro") (part "DB2EVC-3.81-5P"))
    )
    (comp (ref "CN5")
      (value "PLUG_SIDE")
      (footprint "easyedapro:CONN-TH_10P-P3.81_DB2EVC-3.81-10P")
      (fields (field (name "Manufacturer Part") "plug_side") (field (name "Manufacturer") "DORABO(地博电气)"))
      (libsource (lib "easyedapro") (part "DB2EVC-3.81-10P"))
    )
    (comp (ref "CN6")
      (value "PLUG_BATT")
      (footprint "easyedapro:CONN-TH_11P-P3.81_DB2EVC-3.81-11P-GN")
      (fields
        (field (name "Manufacturer Part") "DB2EVC-3.81-11P-GN")
        (field (name "Manufacturer") "DORABO(地博电气)")
      )
      (libsource (lib "easyedapro") (part "DB2EVC-3.81-11P-GN"))
    )
    (comp (ref "CN9")
      (value "PLUG_BSPD")
      (footprint "easyedapro:CONN-TH_4P-P3.81_DB2EVC-3.81-4P")
      (fields (field (name "Manufacturer Part") "plug-bspd") (field (name "Manufacturer") "DORABO(地博电气)"))
      (libsource (lib "easyedapro") (part "DB2EVC-3.81-4P"))
    )
    (comp (ref "CN10")
      (value "PLUG_VCU")
      (footprint "easyedapro:CONN-TH_22P-P3.81_DB2EVC-3.81-22P-GN")
      (fields (field (name "Manufacturer") "DORABO(地博电气)"))
      (libsource (lib "easyedapro") (part "DB2EVC-3.81-22P-GN"))
    )
    (comp (ref "CN11")
      (value "PLUG_HV")
      (footprint "easyedapro:CONN-TH_10P-P3.81_DB2EVC-3.81-10P")
      (fields (field (name "Manufacturer Part") "plug_side") (field (name "Manufacturer") "DORABO(地博电气)"))
      (libsource (lib "easyedapro") (part "DB2EVC-3.81-10P"))
    )
    (comp (ref "BACK")
      (value "09")
      (footprint "easyedapro:LED0805-R-RD")
      (fields (field (name "Manufacturer Part") "NCD0805G1") (field (name "Manufacturer") "国星光电"))
      (libsource (lib "easyedapro") (part "FC-2012UGK-520D5"))
    )
    (comp (ref "BATT")
      (value "10")
      (footprint "easyedapro:LED0805-R-RD")
      (fields (field (name "Manufacturer Part") "NCD0805G1") (field (name "Manufacturer") "国星光电"))
      (libsource (lib "easyedapro") (part "FC-2012UGK-520D5"))
    )
    (comp (ref "BMS")
      (value "03")
      (footprint "easyedapro:LED0805-R-RD")
      (fields (field (name "Manufacturer Part") "NCD0805G1") (field (name "Manufacturer") "国星光电"))
      (libsource (lib "easyedapro") (part "FC-2012UGK-520D5"))
    )
    (comp (ref "BSPD")
      (value "02")
      (footprint "easyedapro:LED0805-R-RD")
      (fields (field (name "Manufacturer Part") "NCD0805G1") (field (name "Manufacturer") "国星光电"))
      (libsource (lib "easyedapro") (part "FC-2012UGK-520D5"))
    )
    (comp (ref "FRONT")
      (value "06")
      (footprint "easyedapro:LED0805-R-RD")
      (fields (field (name "Manufacturer Part") "NCD0805G1") (field (name "Manufacturer") "国星光电"))
      (libsource (lib "easyedapro") (part "FC-2012UGK-520D5"))
    )
    (comp (ref "HV")
      (value "07")
      (footprint "easyedapro:LED0805-R-RD")
      (fields (field (name "Manufacturer Part") "NCD0805G1") (field (name "Manufacturer") "国星光电"))
      (libsource (lib "easyedapro") (part "FC-2012UGK-520D5"))
    )
    (comp (ref "IMD")
      (value "04")
      (footprint "easyedapro:LED0805-R-RD")
      (fields (field (name "Manufacturer Part") "NCD0805G1") (field (name "Manufacturer") "国星光电"))
      (libsource (lib "easyedapro") (part "FC-2012UGK-520D5"))
    )
    (comp (ref "R5")
      (value "10kΩ")
      (footprint "easyedapro:R0603")
      (description "电阻类型:厚膜电阻;阻值:10kΩ;精度:±1%;功率:100mW;最大工作电压:75V;温度系数:±100ppm/°C;")
      (fields
        (field (name "Manufacturer Part") "0603WAF1002T5E")
        (field (name "Manufacturer") "UNI-ROYAL(厚声)")
      )
      (libsource (lib "easyedapro") (part "0603WAF1002T5E"))
    )
    (comp (ref "R9")
      (value "10kΩ")
      (footprint "easyedapro:R0603")
      (description "电阻类型:厚膜电阻;阻值:10kΩ;精度:±1%;功率:100mW;最大工作电压:75V;温度系数:±100ppm/°C;")
      (fields
        (field (name "Manufacturer Part") "0603WAF1002T5E")
        (field (name "Manufacturer") "UNI-ROYAL(厚声)")
      )
      (libsource (lib "easyedapro") (part "0603WAF1002T5E"))
    )
    (comp (ref "R10")
      (value "10kΩ")
      (footprint "easyedapro:R0603")
      (description "电阻类型:厚膜电阻;阻值:10kΩ;精度:±1%;功率:100mW;最大工作电压:75V;温度系数:±100ppm/°C;")
      (fields
        (field (name "Manufacturer Part") "0603WAF1002T5E")
        (field (name "Manufacturer") "UNI-ROYAL(厚声)")
      )
      (libsource (lib "easyedapro") (part "0603WAF1002T5E"))
    )
    (comp (ref "R13")
      (value "10kΩ")
      (footprint "easyedapro:R0603")
      (description "电阻类型:厚膜电阻;阻值:10kΩ;精度:±1%;功率:100mW;最大工作电压:75V;温度系数:±100ppm/°C;")
      (fields
        (field (name "Manufacturer Part") "0603WAF1002T5E")
        (field (name "Manufacturer") "UNI-ROYAL(厚声)")
      )
      (libsource (lib "easyedapro") (part "0603WAF1002T5E"))
    )
    (comp (ref "R16")
      (value "10kΩ")
      (footprint "easyedapro:R0603")
      (description "电阻类型:厚膜电阻;阻值:10kΩ;精度:±1%;功率:100mW;最大工作电压:75V;温度系数:±100ppm/°C;")
      (fields
        (field (name "Manufacturer Part") "0603WAF1002T5E")
        (field (name "Manufacturer") "UNI-ROYAL(厚声)")
      )
      (libsource (lib "easyedapro") (part "0603WAF1002T5E"))
    )
    (comp (ref "R17")
      (value "10kΩ")
      (footprint "easyedapro:R0603")
      (description "电阻类型:厚膜电阻;阻值:10kΩ;精度:±1%;功率:100mW;最大工作电压:75V;温度系数:±100ppm/°C;")
      (fields
        (field (name "Manufacturer Part") "0603WAF1002T5E")
        (field (name "Manufacturer") "UNI-ROYAL(厚声)")
      )
      (libsource (lib "easyedapro") (part "0603WAF1002T5E"))
    )
    (comp (ref "R20")
      (value "10kΩ")
      (footprint "easyedapro:R0603")
      (description "电阻类型:厚膜电阻;阻值:10kΩ;精度:±1%;功率:100mW;最大工作电压:75V;温度系数:±100ppm/°C;")
      (fields
        (field (name "Manufacturer Part") "0603WAF1002T5E")
        (field (name "Manufacturer") "UNI-ROYAL(厚声)")
      )
      (libsource (lib "easyedapro") (part "0603WAF1002T5E"))
    )
    (comp (ref "R21")
      (value "10kΩ")
      (footprint "easyedapro:R0603")
      (description "电阻类型:厚膜电阻;阻值:10kΩ;精度:±1%;功率:100mW;最大工作电压:75V;温度系数:±100ppm/°C;")
      (fields
        (field (name "Manufacturer Part") "0603WAF1002T5E")
        (field (name "Manufacturer") "UNI-ROYAL(厚声)")
      )
      (libsource (lib "easyedapro") (part "0603WAF1002T5E"))
    )
    (comp (ref "R22")
      (value "10kΩ")
      (footprint "easyedapro:R0603")
      (description "电阻类型:厚膜电阻;阻值:10kΩ;精度:±1%;功率:100mW;最大工作电压:75V;温度系数:±100ppm/°C;")
      (fields
        (field (name "Manufacturer Part") "0603WAF1002T5E")
        (field (name "Manufacturer") "UNI-ROYAL(厚声)")
      )
      (libsource (lib "easyedapro") (part "0603WAF1002T5E"))
    )
    (comp (ref "R97")
      (value "2kΩ")
      (footprint "easyedapro:R0603")
      (description "电阻类型:厚膜电阻;阻值:2kΩ;精度:±1%;功率:100mW;最大工作电压:75V;温度系数:±100ppm/°C;")
      (fields
        (field (name "Manufacturer Part") "0603WAF2001T5E")
        (field (name "Manufacturer") "UNI-ROYAL(厚声)")
      )
      (libsource (lib "easyedapro") (part "0603WAF2001T5E"))
    )
    (comp (ref "R98")
      (value "2kΩ")
      (footprint "easyedapro:R0603")
      (description "电阻类型:厚膜电阻;阻值:2kΩ;精度:±1%;功率:100mW;最大工作电压:75V;温度系数:±100ppm/°C;")
      (fields
        (field (name "Manufacturer Part") "0603WAF2001T5E")
        (field (name "Manufacturer") "UNI-ROYAL(厚声)")
      )
      (libsource (lib "easyedapro") (part "0603WAF2001T5E"))
    )
    (comp (ref "R99")
      (value "2kΩ")
      (footprint "easyedapro:R0603")
      (description "电阻类型:厚膜电阻;阻值:2kΩ;精度:±1%;功率:100mW;最大工作电压:75V;温度系数:±100ppm/°C;")
      (fields
        (field (name "Manufacturer Part") "0603WAF2001T5E")
        (field (name "Manufacturer") "UNI-ROYAL(厚声)")
      )
      (libsource (lib "easyedapro") (part "0603WAF2001T5E"))
    )
    (comp (ref "R100")
      (value "2kΩ")
      (footprint "easyedapro:R0603")
      (description "电阻类型:厚膜电阻;阻值:2kΩ;精度:±1%;功率:100mW;最大工作电压:75V;温度系数:±100ppm/°C;")
      (fields
        (field (name "Manufacturer Part") "0603WAF2001T5E")
        (field (name "Manufacturer") "UNI-ROYAL(厚声)")
      )
      (libsource (lib "easyedapro") (part "0603WAF2001T5E"))
    )
    (comp (ref "R101")
      (value "2kΩ")
      (footprint "easyedapro:R0603")
      (description "电阻类型:厚膜电阻;阻值:2kΩ;精度:±1%;功率:100mW;最大工作电压:75V;温度系数:±100ppm/°C;")
      (fields
        (field (name "Manufacturer Part") "0603WAF2001T5E")
        (field (name "Manufacturer") "UNI-ROYAL(厚声)")
      )
      (libsource (lib "easyedapro") (part "0603WAF2001T5E"))
    )
    (comp (ref "R102")
      (value "2kΩ")
      (footprint "easyedapro:R0603")
      (description "电阻类型:厚膜电阻;阻值:2kΩ;精度:±1%;功率:100mW;最大工作电压:75V;温度系数:±100ppm/°C;")
      (fields
        (field (name "Manufacturer Part") "0603WAF2001T5E")
        (field (name "Manufacturer") "UNI-ROYAL(厚声)")
      )
      (libsource (lib "easyedapro") (part "0603WAF2001T5E"))
    )
    (comp (ref "R103")
      (value "2kΩ")
      (footprint "easyedapro:R0603")
      (description "电阻类型:厚膜电阻;阻值:2kΩ;精度:±1%;功率:100mW;最大工作电压:75V;温度系数:±100ppm/°C;")
      (fields
        (field (name "Manufacturer Part") "0603WAF2001T5E")
        (field (name "Manufacturer") "UNI-ROYAL(厚声)")
      )
      (libsource (lib "easyedapro") (part "0603WAF2001T5E"))
    )
    (comp (ref "R104")
      (value "2kΩ")
      (footprint "easyedapro:R0603")
      (description "电阻类型:厚膜电阻;阻值:2kΩ;精度:±1%;功率:100mW;最大工作电压:75V;温度系数:±100ppm/°C;")
      (fields
        (field (name "Manufacturer Part") "0603WAF2001T5E")
        (field (name "Manufacturer") "UNI-ROYAL(厚声)")
      )
      (libsource (lib "easyedapro") (part "0603WAF2001T5E"))
    )
    (comp (ref "R105")
      (value "2kΩ")
      (footprint "easyedapro:R0603")
      (description "电阻类型:厚膜电阻;阻值:2kΩ;精度:±1%;功率:100mW;最大工作电压:75V;温度系数:±100ppm/°C;")
      (fields
        (field (name "Manufacturer Part") "0603WAF2001T5E")
        (field (name "Manufacturer") "UNI-ROYAL(厚声)")
      )
      (libsource (lib "easyedapro") (part "0603WAF2001T5E"))
    )
    (comp (ref "R107")
      (value "10kΩ")
      (footprint "easyedapro:R0603")
      (description "电阻类型:厚膜电阻;阻值:10kΩ;精度:±1%;功率:100mW;最大工作电压:75V;温度系数:±100ppm/°C;")
      (fields
        (field (name "Manufacturer Part") "0603WAF1002T5E")
        (field (name "Manufacturer") "UNI-ROYAL(厚声)")
      )
      (libsource (lib "easyedapro") (part "0603WAF1002T5E"))
    )
    (comp (ref "R108")
      (value "20kΩ")
      (footprint "easyedapro:R0603")
      (description "电阻类型:厚膜电阻;阻值:20kΩ;精度:±1%;功率:100mW;最大工作电压:75V;温度系数:±100ppm/°C;")
      (fields
        (field (name "Manufacturer Part") "0603WAF2002T5E")
        (field (name "Manufacturer") "UNI-ROYAL(厚声)")
      )
      (libsource (lib "easyedapro") (part "0603WAF2002T5E"))
    )
    (comp (ref "R109")
      (value "40kΩ")
      (footprint "easyedapro:R0603")
      (description "电阻类型:薄膜电阻;阻值:40kΩ;精度:±0.1%;功率:100mW;温度系数:±25ppm/°C;")
      (fields (field (name "Manufacturer Part") "RT0603BRD0740KL") (field (name "Manufacturer") "YAGEO(国巨)"))
      (libsource (lib "easyedapro") (part "RT0603BRD0740KL"))
    )
    (comp (ref "R110")
      (value "80kΩ")
      (footprint "easyedapro:R0603")
      (description "阻值:80kΩ;精度:±1%;功率:100mW;温度系数:±25ppm/°C;")
      (fields (field (name "Manufacturer Part") "ARG03FTC8002N") (field (name "Manufacturer") "Viking(光颉)"))
      (libsource (lib "easyedapro") (part "ARG03FTC8002N"))
    )
    (comp (ref "R111")
      (value "100kΩ")
      (footprint "easyedapro:R0603")
      (description "电阻类型:厚膜电阻;阻值:100kΩ;精度:±1%;功率:100mW;最大工作电压:75V;温度系数:±100ppm/°C;")
      (fields
        (field (name "Manufacturer Part") "0603WAF1003T5E")
        (field (name "Manufacturer") "UNI-ROYAL(厚声)")
      )
      (libsource (lib "easyedapro") (part "0603WAF1003T5E"))
    )
    (comp (ref "R112")
      (value "10kΩ")
      (footprint "easyedapro:R0603")
      (description "电阻类型:厚膜电阻;阻值:10kΩ;精度:±1%;功率:100mW;最大工作电压:75V;温度系数:±100ppm/°C;")
      (fields
        (field (name "Manufacturer Part") "0603WAF1002T5E")
        (field (name "Manufacturer") "UNI-ROYAL(厚声)")
      )
      (libsource (lib "easyedapro") (part "0603WAF1002T5E"))
    )
    (comp (ref "R113")
      (value "2kΩ")
      (footprint "easyedapro:R0603")
      (description "电阻类型:厚膜电阻;阻值:2kΩ;精度:±1%;功率:100mW;最大工作电压:75V;温度系数:±100ppm/°C;")
      (fields
        (field (name "Manufacturer Part") "0603WAF2001T5E")
        (field (name "Manufacturer") "UNI-ROYAL(厚声)")
      )
      (libsource (lib "easyedapro") (part "0603WAF2001T5E"))
    )
    (comp (ref "RING")
      (value "05")
      (footprint "easyedapro:LED0805-R-RD")
      (fields (field (name "Manufacturer Part") "NCD0805G1") (field (name "Manufacturer") "国星光电"))
      (libsource (lib "easyedapro") (part "FC-2012UGK-520D5"))
    )
    (comp (ref "SIDE")
      (value "08")
      (footprint "easyedapro:LED0805-R-RD")
      (fields (field (name "Manufacturer Part") "NCD0805G1") (field (name "Manufacturer") "国星光电"))
      (libsource (lib "easyedapro") (part "FC-2012UGK-520D5"))
    )
    (comp (ref "SWLB+")
      (value "02")
      (footprint "easyedapro:LED0805-R-RD")
      (fields (field (name "Manufacturer Part") "NCD0805G1") (field (name "Manufacturer") "国星光电"))
      (libsource (lib "easyedapro") (part "FC-2012UGK-520D5"))
    )
    (comp (ref "U3")
      (value "SN74LS147N(LX)")
      (footprint "easyedapro:PDIP-16_L19.3-W6.4-P2.54-LS7.94-BL")
      (description "供电电压:2V~6V;线路数:4~10;灌电流(IOL):5.2mA;拉电流(IOH):5.2mA;")
      (fields (field (name "Manufacturer") "LX(灵星芯微)"))
      (libsource (lib "easyedapro") (part "SN74LS147N(LX)"))
    )
  )
  (nets
    (net (code "1") (name "+0.16V_1") (class "Default")
      (node (ref "R64") (pin "1") (pinfunction "1_1") (pintype "input"))
      (node (ref "R66") (pin "2") (pinfunction "2_2") (pintype "input"))
      (node (ref "电压比较器1") (pin "10") (pinfunction "IN-_10") (pintype "input"))
    )
    (net (code "2") (name "+0.16V_2") (class "Default")
      (node (ref "R87") (pin "1") (pinfunction "1_1") (pintype "input"))
      (node (ref "R88") (pin "2") (pinfunction "2_2") (pintype "input"))
      (node (ref "电压比较器2") (pin "4") (pinfunction "IN-_4") (pintype "input"))
    )
    (net (code "3") (name "+0.16V_3") (class "Default")
      (node (ref "R58") (pin "2") (pinfunction "2_2") (pintype "input"))
      (node (ref "R59") (pin "1") (pinfunction "1_1") (pintype "input"))
      (node (ref "电压比较器3") (pin "6") (pinfunction "IN-_6") (pintype "input"))
      (node (ref "电压比较器3") (pin "8") (pinfunction "IN-_8") (pintype "input"))
    )
    (net (code "4") (name "+4.55V_1") (class "Default")
      (node (ref "R63") (pin "1") (pinfunction "1_1") (pintype "input"))
      (node (ref "R65") (pin "2") (pinfunction "2_2") (pintype "input"))
      (node (ref "电压比较器1") (pin "7") (pinfunction "IN+_7") (pintype "input"))
    )
    (net (code "5") (name "+4.55V_2") (class "Default")
      (node (ref "R85") (pin "1") (pinfunction "1_1") (pintype "input"))
      (node (ref "R86") (pin "2") (pinfunction "2_2") (pintype "input"))
      (node (ref "电压比较器2") (pin "6") (pinfunction "IN-_6") (pintype "input"))
    )
    (net (code "6") (name "+4.55V_3") (class "Default")
      (node (ref "R60") (pin "2") (pinfunction "2_2") (pintype "input"))
      (node (ref "R61") (pin "1") (pinfunction "1_1") (pintype "input"))
      (node (ref "电压比较器3") (pin "11") (pinfunction "IN+_11") (pintype "input"))
    )
    (net (code "7") (name "+4.55V_4") (class "Default")
      (node (ref "R89") (pin "1") (pinfunction "1_1") (pintype "input"))
      (node (ref "R90") (pin "2") (pinfunction "2_2") (pintype "input"))
      (node (ref "电压比较器4") (pin "10") (pinfunction "IN-_10") (pintype "input"))
      (node (ref "电压比较器4") (pin "6") (pinfunction "IN-_6") (pintype "input"))
      (node (ref "电压比较器4") (pin "8") (pinfunction "IN-_8") (pintype "input"))
    )
    (net (code "8") (name "+4.55V_5") (class "Default")
      (node (ref "R37") (pin "2") (pinfunction "2_2") (pintype "input"))
      (node (ref "R38") (pin "1") (pinfunction "1_1") (pintype "input"))
      (node (ref "电压比较器5") (pin "10") (pinfunction "IN-_10") (pintype "input"))
      (node (ref "电压比较器5") (pin "4") (pinfunction "IN-_4") (pintype "input"))
      (node (ref "电压比较器5") (pin "7") (pinfunction "IN+_7") (pintype "input"))
    )
    (net (code "9") (name "+5V") (class "Default")
      (node (ref "C4") (pin "2") (pinfunction "2_2") (pintype "input"))
      (node (ref "C8") (pin "2") (pinfunction "2_2") (pintype "unspecified"))
      (node (ref "CN1") (pin "2") (pinfunction "2_2") (pintype "unspecified"))
      (node (ref "CN2") (pin "2") (pinfunction "2_2") (pintype "unspecified"))
      (node (ref "CN5") (pin "1") (pinfunction "1_1") (pintype "unspecified"))
      (node (ref "DC/DC1") (pin "3") (pinfunction "+Vo_3") (pintype "unspecified"))
      (node (ref "PMOS2") (pin "2") (pinfunction "S_2") (pintype "unspecified"))
      (node (ref "PMOS3") (pin "2") (pinfunction "S_2") (pintype "unspecified"))
      (node (ref "PMOS4") (pin "2") (pinfunction "S_2") (pintype "unspecified"))
      (node (ref "PMOS5") (pin "2") (pinfunction "S_2") (pintype "unspecified"))
      (node (ref "R11") (pin "2") (pinfunction "2_2") (pintype "input"))
      (node (ref "R18") (pin "2") (pinfunction "2_2") (pintype "input"))
      (node (ref "R19") (pin "2") (pinfunction "2_2") (pintype "input"))
      (node (ref "R23") (pin "2") (pinfunction "2_2") (pintype "input"))
      (node (ref "R24") (pin "2") (pinfunction "2_2") (pintype "input"))
      (node (ref "R29") (pin "2") (pinfunction "2_2") (pintype "input"))
      (node (ref "R30") (pin "2") (pinfunction "2_2") (pintype "input"))
      (node (ref "R32") (pin "2") (pinfunction "2_2") (pintype "input"))
      (node (ref "R35") (pin "2") (pinfunction "2_2") (pintype "input"))
      (node (ref "R36") (pin "2") (pinfunction "2_2") (pintype "input"))
      (node (ref "R38") (pin "2") (pinfunction "2_2") (pintype "input"))
      (node (ref "R4") (pin "2") (pinfunction "2_2") (pintype "input"))
      (node (ref "R43") (pin "2") (pinfunction "2_2") (pintype "input"))
      (node (ref "R59") (pin "2") (pinfunction "2_2") (pintype "input"))
      (node (ref "R61") (pin "2") (pinfunction "2_2") (pintype "input"))
      (node (ref "R63") (pin "2") (pinfunction "2_2") (pintype "input"))
      (node (ref "R64") (pin "2") (pinfunction "2_2") (pintype "input"))
      (node (ref "R72") (pin "2") (pinfunction "2_2") (pintype "input"))
      (node (ref "R76") (pin "2") (pinfunction "2_2") (pintype "input"))
      (node (ref "R77") (pin "2") (pinfunction "2_2") (pintype "input"))
      (node (ref "R85") (pin "2") (pinfunction "2_2") (pintype "input"))
      (node (ref "R87") (pin "2") (pinfunction "2_2") (pintype "input"))
      (node (ref "R89") (pin "2") (pinfunction "2_2") (pintype "input"))
      (node (ref "U1") (pin "4") (pinfunction "RESET_4") (pintype "unspecified"))
      (node (ref "U1") (pin "8") (pinfunction "VCC_8") (pintype "unspecified"))
      (node (ref "U3") (pin "16") (pinfunction "VCC_16") (pintype "unspecified"))
      (node (ref "可调电阻1") (pin "3") (pinfunction "3_3") (pintype "unspecified"))
      (node (ref "可调电阻2") (pin "3") (pinfunction "3_3") (pintype "unspecified"))
      (node (ref "可调电阻3") (pin "3") (pinfunction "3_3") (pintype "unspecified"))
      (node (ref "继电器1") (pin "3") (pinfunction "3_3") (pintype "unspecified"))
      (node (ref "继电器2") (pin "3") (pinfunction "3_3") (pintype "unspecified"))
    )
    (net (code "10") (name "+18V_1") (class "Default")
      (node (ref "R71") (pin "2") (pinfunction "2_2") (pintype "input"))
      (node (ref "R75") (pin "1") (pinfunction "1_1") (pintype "input"))
      (node (ref "电压比较器4") (pin "5") (pinfunction "IN+_5") (pintype "input"))
    )
    (net (code "11") (name "+18V_2") (class "Default")
      (node (ref "R27") (pin "2") (pinfunction "2_2") (pintype "input"))
      (node (ref "R28") (pin "1") (pinfunction "1_1") (pintype "input"))
      (node (ref "电压比较器6") (pin "4") (pinfunction "IN-_4") (pintype "input"))
      (node (ref "电压比较器6") (pin "6") (pinfunction "IN-_6") (pintype "input"))
    )
    (net (code "12") (name "+24V") (class "Default")
      (node (ref "CN1") (pin "1") (pinfunction "1_1") (pintype "unspecified"))
      (node (ref "CN11") (pin "1") (pinfunction "1_1") (pintype "unspecified"))
      (node (ref "CN2") (pin "1") (pinfunction "1_1") (pintype "unspecified"))
      (node (ref "CN4") (pin "1") (pinfunction "1_1") (pintype "unspecified"))
      (node (ref "CN6") (pin "1") (pinfunction "1_1") (pintype "unspecified"))
      (node (ref "PMOS8") (pin "2") (pinfunction "S_2") (pintype "unspecified"))
      (node (ref "R28") (pin "2") (pinfunction "2_2") (pintype "input"))
      (node (ref "R39") (pin "2") (pinfunction "2_2") (pintype "input"))
      (node (ref "R40") (pin "2") (pinfunction "2_2") (pintype "input"))
      (node (ref "R49") (pin "2") (pinfunction "2_2") (pintype "input"))
      (node (ref "R75") (pin "2") (pinfunction "2_2") (pintype "input"))
      (node (ref "R8") (pin "2") (pinfunction "2_2") (pintype "input"))
      (node (ref "R82") (pin "2") (pinfunction "2_2") (pintype "input"))
      (node (ref "TSALGREEN") (pin "1") (pinfunction "A_1") (pintype "unspecified"))
      (node (ref "TSALRED") (pin "1") (pinfunction "+_1") (pintype "unspecified"))
      (node (ref "U2") (pin "7") (pinfunction "+Vo_7") (pintype "input"))
      (node (ref "U2") (pin "8") (pinfunction "+Vo_8") (pintype "input"))
      (node (ref "电压比较器1") (pin "3") (pinfunction "VCC_3") (pintype "unspecified"))
      (node (ref "电压比较器2") (pin "3") (pinfunction "VCC_3") (pintype "unspecified"))
      (node (ref "电压比较器3") (pin "3") (pinfunction "VCC_3") (pintype "unspecified"))
      (node (ref "电压比较器4") (pin "3") (pinfunction "VCC_3") (pintype "unspecified"))
      (node (ref "电压比较器5") (pin "3") (pinfunction "VCC_3") (pintype "unspecified"))
      (node (ref "电压比较器6") (pin "3") (pinfunction "VCC_3") (pintype "unspecified"))
    )
    (net (code "13") (name "AIR") (class "Default")
      (node (ref "CN6") (pin "7") (pinfunction "7_7") (pintype "unspecified"))
      (node (ref "R73") (pin "2") (pinfunction "2_2") (pintype "input"))
      (node (ref "电压比较器4") (pin "4") (pinfunction "IN-_4") (pintype "input"))
      (node (ref "电压比较器4") (pin "7") (pinfunction "IN+_7") (pintype "input"))
    )
    (net (code "14") (name "APPS1") (class "Default")
      (node (ref "CN1") (pin "11") (pinfunction "11_11") (pintype "unspecified"))
      (node (ref "CN10") (pin "14") (pinfunction "14_14") (pintype "unspecified"))
    )
    (net (code "15") (name "APPS2") (class "Default")
      (node (ref "CN1") (pin "12") (pinfunction "12_12") (pintype "unspecified"))
      (node (ref "CN10") (pin "15") (pinfunction "15_15") (pintype "unspecified"))
    )
    (net (code "16") (name "BATT_VOLT") (class "Default")
      (node (ref "CN6") (pin "6") (pinfunction "6_6") (pintype "unspecified"))
      (node (ref "R74") (pin "2") (pinfunction "2_2") (pintype "input"))
      (node (ref "电压比较器3") (pin "10") (pinfunction "IN-_10") (pintype "input"))
      (node (ref "电压比较器3") (pin "4") (pinfunction "IN-_4") (pintype "input"))
      (node (ref "电压比较器3") (pin "7") (pinfunction "IN+_7") (pintype "input"))
    )
    (net (code "17") (name "BATT_VOLT_REF") (class "Default")
      (node (ref "可调电阻1") (pin "2") (pinfunction "2_2") (pintype "unspecified"))
      (node (ref "电压比较器3") (pin "5") (pinfunction "IN+_5") (pintype "input"))
    )
    (net (code "18") (name "BMS") (class "Default")
      (node (ref "CN6") (pin "4") (pinfunction "4_4") (pintype "unspecified"))
      (node (ref "R84") (pin "2") (pinfunction "2_2") (pintype "input"))
      (node (ref "电压比较器6") (pin "5") (pinfunction "IN+_5") (pintype "input"))
    )
    (net (code "19") (name "BMS_ERROR") (class "Default")
      (node (ref "CN1") (pin "6") (pinfunction "6_6") (pintype "unspecified"))
      (node (ref "PMOS2") (pin "3") (pinfunction "D_3") (pintype "unspecified"))
      (node (ref "继电器1") (pin "2") (pinfunction "2_2") (pintype "unspecified"))
    )
    (net (code "20") (name "BMS_RESET-") (class "Default")
      (node (ref "CN5") (pin "2") (pinfunction "2_2") (pintype "unspecified"))
      (node (ref "D1") (pin "1") (pinfunction "C_1") (pintype "unspecified"))
      (node (ref "PMOS4") (pin "3") (pinfunction "D_3") (pintype "unspecified"))
      (node (ref "继电器1") (pin "1") (pinfunction "1_1") (pintype "unspecified"))
      (node (ref "继电器1") (pin "4") (pinfunction "4_4") (pintype "unspecified"))
    )
    (net (code "21") (name "BRAKELIGHT-") (class "Default")
      (node (ref "CN2") (pin "4") (pinfunction "4_4") (pintype "unspecified"))
      (node (ref "NMOS4") (pin "3") (pinfunction "D_3") (pintype "unspecified"))
    )
    (net (code "22") (name "BRAKE_PEDAL") (class "Default")
      (node (ref "CN1") (pin "15") (pinfunction "15_15") (pintype "unspecified"))
      (node (ref "CN10") (pin "18") (pinfunction "18_18") (pintype "unspecified"))
    )
    (net (code "23") (name "BRAKE_VOLT_B") (class "Default")
      (node (ref "CN10") (pin "13") (pinfunction "13_13") (pintype "unspecified"))
      (node (ref "CN2") (pin "5") (pinfunction "5_5") (pintype "unspecified"))
      (node (ref "电压比较器2") (pin "11") (pinfunction "IN+_11") (pintype "input"))
    )
    (net (code "24") (name "BRAKE_VOLT_F") (class "Default")
      (node (ref "CN1") (pin "13") (pinfunction "13_13") (pintype "unspecified"))
      (node (ref "CN10") (pin "16") (pinfunction "16_16") (pintype "unspecified"))
    )
    (net (code "25") (name "BRAKE_VOLT_REF") (class "Default")
      (node (ref "可调电阻3") (pin "2") (pinfunction "2_2") (pintype "unspecified"))
      (node (ref "电压比较器2") (pin "10") (pinfunction "IN-_10") (pintype "input"))
    )
    (net (code "26") (name "BUZZER") (class "Default")
      (node (ref "CN1") (pin "14") (pinfunction "14_14") (pintype "unspecified"))
      (node (ref "CN10") (pin "17") (pinfunction "17_17") (pintype "unspecified"))
    )
    (net (code "27") (name "CHAR+") (class "Default")
      (node (ref "CN5") (pin "7") (pinfunction "7_7") (pintype "unspecified"))
    )
    (net (code "28") (name "CLOCK") (class "Default")
      (node (ref "R15") (pin "2") (pinfunction "2_2") (pintype "input"))
      (node (ref "U1") (pin "3") (pinfunction "OUT_3") (pintype "unspecified"))
    )
    (net (code "29") (name "CURRENT") (class "Default")
      (node (ref "CN10") (pin "19") (pinfunction "19_19") (pintype "unspecified"))
      (node (ref "CN11") (pin "6") (pinfunction "6_6") (pintype "unspecified"))
    )
    (net (code "30") (name "CURRENT_FOR_INSPECTION") (class "Default")
      (node (ref "CN11") (pin "7") (pinfunction "7_7") (pintype "unspecified"))
      (node (ref "CN5") (pin "6") (pinfunction "6_6") (pintype "unspecified"))
    )
    (net (code "31") (name "DCDC_ENABLE") (class "Default")
      (node (ref "CN10") (pin "8") (pinfunction "8_8") (pintype "unspecified"))
      (node (ref "CN11") (pin "5") (pinfunction "5_5") (pintype "unspecified"))
    )
    (net (code "32") (name "DCDC_TEMP") (class "Default")
      (node (ref "CN10") (pin "20") (pinfunction "20_20") (pintype "unspecified"))
      (node (ref "CN11") (pin "10") (pinfunction "10_10") (pintype "unspecified"))
    )
    (net (code "33") (name "FAN_PWM-") (class "Default")
      (node (ref "CN1") (pin "19") (pinfunction "19_19") (pintype "unspecified"))
      (node (ref "CN2") (pin "11") (pinfunction "11_11") (pintype "unspecified"))
      (node (ref "D5") (pin "2") (pinfunction "A_2") (pintype "unspecified"))
      (node (ref "Q2") (pin "4") (pinfunction "D_4") (pintype "unspecified"))
    )
    (net (code "34") (name "FAN_SWITCH") (class "Default")
      (node (ref "CN1") (pin "20") (pinfunction "20_20") (pintype "unspecified"))
      (node (ref "R94") (pin "2") (pinfunction "2_2") (pintype "input"))
    )
    (net (code "35") (name "FUSED_LOW_BATT+") (class "Default")
      (node (ref "CN5") (pin "9") (pinfunction "9_9") (pintype "unspecified"))
      (node (ref "FH1") (pin "1") (pinfunction "1_1") (pintype "unspecified"))
    )
    (net (code "36") (name "GND") (class "Default")
      (node (ref "C10") (pin "2") (pinfunction "2_2") (pintype "unspecified"))
      (node (ref "C2") (pin "1") (pinfunction "1_1") (pintype "unspecified"))
      (node (ref "C3") (pin "2") (pinfunction "2_2") (pintype "input"))
      (node (ref "C4") (pin "1") (pinfunction "1_1") (pintype "input"))
      (node (ref "C5") (pin "1") (pinfunction "1_1") (pintype "input"))
      (node (ref "C6") (pin "1") (pinfunction "1_1") (pintype "unspecified"))
      (node (ref "C7") (pin "1") (pinfunction "1_1") (pintype "unspecified"))
      (node (ref "C9") (pin "2") (pinfunction "2_2") (pintype "unspecified"))
      (node (ref "CN1") (pin "3") (pinfunction "3_3") (pintype "unspecified"))
      (node (ref "CN10") (pin "4") (pinfunction "4_4") (pintype "unspecified"))
      (node (ref "CN10") (pin "5") (pinfunction "5_5") (pintype "unspecified"))
      (node (ref "CN10") (pin "6") (pinfunction "6_6") (pintype "unspecified"))
      (node (ref "CN11") (pin "2") (pinfunction "2_2") (pintype "unspecified"))
      (node (ref "CN2") (pin "3") (pinfunction "3_3") (pintype "unspecified"))
      (node (ref "CN5") (pin "8") (pinfunction "8_8") (pintype "unspecified"))
      (node (ref "CN6") (pin "2") (pinfunction "2_2") (pintype "unspecified"))
      (node (ref "CN7") (pin "2") (pinfunction "2_2") (pintype "unspecified"))
      (node (ref "CN9") (pin "2") (pinfunction "2_2") (pintype "unspecified"))
      (node (ref "DC/DC1") (pin "2") (pinfunction "GND_2") (pintype "unspecified"))
      (node (ref "LED1") (pin "2") (pinfunction "-_2") (pintype "unspecified"))
      (node (ref "LED2") (pin "2") (pinfunction "-_2") (pintype "unspecified"))
      (node (ref "NMOS1") (pin "2") (pinfunction "S_2") (pintype "unspecified"))
      (node (ref "NMOS2") (pin "2") (pinfunction "S_2") (pintype "unspecified"))
      (node (ref "NMOS3") (pin "2") (pinfunction "S_2") (pintype "unspecified"))
      (node (ref "NMOS4") (pin "2") (pinfunction "S_2") (pintype "unspecified"))
      (node (ref "NMOS6") (pin "2") (pinfunction "S_2") (pintype "unspecified"))
      (node (ref "NMOS7") (pin "2") (pinfunction "S_2") (pintype "unspecified"))
      (node (ref "NMOS8") (pin "2") (pinfunction "S_2") (pintype "unspecified"))
      (node (ref "Q1") (pin "3") (pinfunction "S_3") (pintype "unspecified"))
      (node (ref "Q2") (pin "3") (pinfunction "S_3") (pintype "unspecified"))
      (node (ref "R100") (pin "1") (pinfunction "1_1") (pintype "input"))
      (node (ref "R101") (pin "1") (pinfunction "1_1") (pintype "input"))
      (node (ref "R102") (pin "1") (pinfunction "1_1") (pintype "input"))
      (node (ref "R103") (pin "1") (pinfunction "1_1") (pintype "input"))
      (node (ref "R104") (pin "1") (pinfunction "1_1") (pintype "input"))
      (node (ref "R105") (pin "1") (pinfunction "1_1") (pintype "input"))
      (node (ref "R111") (pin "1") (pinfunction "1_1") (pintype "input"))
      (node (ref "R113") (pin "1") (pinfunction "1_1") (pintype "input"))
      (node (ref "R14") (pin "1") (pinfunction "1_1") (pintype "input"))
      (node (ref "R27") (pin "1") (pinfunction "1_1") (pintype "input"))
      (node (ref "R31") (pin "1") (pinfunction "1_1") (pintype "input"))
      (node (ref "R37") (pin "1") (pinfunction "1_1") (pintype "input"))
      (node (ref "R51") (pin "1") (pinfunction "1_1") (pintype "input"))
      (node (ref "R52") (pin "1") (pinfunction "1_1") (pintype "input"))
      (node (ref "R58") (pin "1") (pinfunction "1_1") (pintype "input"))
      (node (ref "R60") (pin "1") (pinfunction "1_1") (pintype "input"))
      (node (ref "R65") (pin "1") (pinfunction "1_1") (pintype "input"))
      (node (ref "R66") (pin "1") (pinfunction "1_1") (pintype "input"))
      (node (ref "R7") (pin "1") (pinfunction "1_1") (pintype "input"))
      (node (ref "R71") (pin "1") (pinfunction "1_1") (pintype "input"))
      (node (ref "R73") (pin "1") (pinfunction "1_1") (pintype "input"))
      (node (ref "R74") (pin "1") (pinfunction "1_1") (pintype "input"))
      (node (ref "R83") (pin "1") (pinfunction "1_1") (pintype "input"))
      (node (ref "R84") (pin "1") (pinfunction "1_1") (pintype "input"))
      (node (ref "R86") (pin "1") (pinfunction "1_1") (pintype "input"))
      (node (ref "R88") (pin "1") (pinfunction "1_1") (pintype "input"))
      (node (ref "R90") (pin "1") (pinfunction "1_1") (pintype "input"))
      (node (ref "R91") (pin "1") (pinfunction "1_1") (pintype "input"))
      (node (ref "R93") (pin "1") (pinfunction "1_1") (pintype "input"))
      (node (ref "R97") (pin "1") (pinfunction "1_1") (pintype "input"))
      (node (ref "R98") (pin "1") (pinfunction "1_1") (pintype "input"))
      (node (ref "R99") (pin "1") (pinfunction "1_1") (pintype "input"))
      (node (ref "SW2") (pin "3") (pinfunction "3_3") (pintype "unspecified"))
      (node (ref "SW2") (pin "4") (pinfunction "4_4") (pintype "unspecified"))
      (node (ref "SW2") (pin "5") (pinfunction "5_5") (pintype "unspecified"))
      (node (ref "U1") (pin "1") (pinfunction "GND_1") (pintype "unspecified"))
      (node (ref "U2") (pin "11") (pinfunction "0V_11") (pintype "input"))
      (node (ref "U2") (pin "12") (pinfunction "0V_12") (pintype "input"))
      (node (ref "U2") (pin "5") (pinfunction "-Vin_5") (pintype "input"))
      (node (ref "U2") (pin "6") (pinfunction "-Vin_6") (pintype "input"))
      (node (ref "U3") (pin "8") (pinfunction "GND_8") (pintype "unspecified"))
      (node (ref "可调电阻1") (pin "1") (pinfunction "1_1") (pintype "unspecified"))
      (node (ref "可调电阻2") (pin "1") (pinfunction "1_1") (pintype "unspecified"))
      (node (ref "可调电阻3") (pin "1") (pinfunction "1_1") (pintype "unspecified"))
      (node (ref "电压比较器1") (pin "12") (pinfunction "GND_12") (pintype "unspecified"))
      (node (ref "电压比较器2") (pin "12") (pinfunction "GND_12") (pintype "unspecified"))
      (node (ref "电压比较器3") (pin "12") (pinfunction "GND_12") (pintype "unspecified"))
      (node (ref "电压比较器4") (pin "12") (pinfunction "GND_12") (pintype "unspecified"))
      (node (ref "电压比较器5") (pin "12") (pinfunction "GND_12") (pintype "unspecified"))
      (node (ref "电压比较器6") (pin "12") (pinfunction "GND_12") (pintype "unspecified"))
    )
    (net (code "37") (name "GREENLIGHT_ON") (class "Default")
      (node (ref "R72") (pin "1") (pinfunction "1_1") (pintype "input"))
      (node (ref "电压比较器3") (pin "2") (pinfunction "OUT_2") (pintype "unspecified"))
      (node (ref "电压比较器4") (pin "11") (pinfunction "IN+_11") (pintype "input"))
      (node (ref "电压比较器4") (pin "2") (pinfunction "OUT_2") (pintype "unspecified"))
    )
    (net (code "38") (name "GREEN_SCS_NORMAL") (class "Default")
      (node (ref "R62") (pin "1") (pinfunction "1_1") (pintype "input"))
      (node (ref "R77") (pin "1") (pinfunction "1_1") (pintype "input"))
      (node (ref "电压比较器3") (pin "1") (pinfunction "OUT_1") (pintype "unspecified"))
      (node (ref "电压比较器3") (pin "13") (pinfunction "OUT_13") (pintype "unspecified"))
      (node (ref "电压比较器3") (pin "14") (pinfunction "OUT_14") (pintype "unspecified"))
      (node (ref "电压比较器4") (pin "1") (pinfunction "OUT_1") (pintype "unspecified"))
      (node (ref "电压比较器4") (pin "9") (pinfunction "IN+_9") (pintype "input"))
    )
    (net (code "39") (name "HV_BUTTON-") (class "Default")
      (node (ref "CN1") (pin "4") (pinfunction "4_4") (pintype "unspecified"))
      (node (ref "R42") (pin "1") (pinfunction "1_1") (pintype "input"))
    )
    (net (code "40") (name "HV_ENABLE_IN") (class "Default")
      (node (ref "CN10") (pin "10") (pinfunction "10_10") (pintype "unspecified"))
      (node (ref "R53") (pin "2") (pinfunction "2_2") (pintype "input"))
    )
    (net (code "41") (name "HV_ENABLE_OUT") (class "Default")
      (node (ref "CN6") (pin "3") (pinfunction "3_3") (pintype "unspecified"))
      (node (ref "PMOS8") (pin "3") (pinfunction "D_3") (pintype "unspecified"))
      (node (ref "R52") (pin "2") (pinfunction "2_2") (pintype "input"))
    )
    (net (code "42") (name "HV_ENABLE_TO_VCU") (class "Default")
      (node (ref "C9") (pin "1") (pinfunction "1_1") (pintype "unspecified"))
      (node (ref "CN10") (pin "11") (pinfunction "11_11") (pintype "unspecified"))
      (node (ref "R40") (pin "1") (pinfunction "1_1") (pintype "input"))
      (node (ref "R42") (pin "2") (pinfunction "2_2") (pintype "input"))
    )
    (net (code "43") (name "IMD") (class "Default")
      (node (ref "CN6") (pin "5") (pinfunction "5_5") (pintype "unspecified"))
      (node (ref "R31") (pin "2") (pinfunction "2_2") (pintype "input"))
      (node (ref "电压比较器6") (pin "7") (pinfunction "IN+_7") (pintype "input"))
    )
    (net (code "44") (name "IMD_ERROR") (class "Default")
      (node (ref "CN1") (pin "7") (pinfunction "7_7") (pintype "unspecified"))
      (node (ref "PMOS3") (pin "3") (pinfunction "D_3") (pintype "unspecified"))
      (node (ref "继电器2") (pin "2") (pinfunction "2_2") (pintype "unspecified"))
    )
    (net (code "45") (name "IMD_RESET-") (class "Default")
      (node (ref "CN5") (pin "3") (pinfunction "3_3") (pintype "unspecified"))
      (node (ref "D2") (pin "1") (pinfunction "C_1") (pintype "unspecified"))
      (node (ref "PMOS5") (pin "3") (pinfunction "D_3") (pintype "unspecified"))
      (node (ref "继电器2") (pin "1") (pinfunction "1_1") (pintype "unspecified"))
      (node (ref "继电器2") (pin "4") (pinfunction "4_4") (pintype "unspecified"))
    )
    (net (code "46") (name "INVERTER_BUTTON-") (class "Default")
      (node (ref "CN1") (pin "5") (pinfunction "5_5") (pintype "unspecified"))
      (node (ref "R41") (pin "1") (pinfunction "1_1") (pintype "input"))
    )
    (net (code "47") (name "INVERTER_ENABLE_TO_VCU") (class "Default")
      (node (ref "C10") (pin "1") (pinfunction "1_1") (pintype "unspecified"))
      (node (ref "CN10") (pin "12") (pinfunction "12_12") (pintype "unspecified"))
      (node (ref "R39") (pin "1") (pinfunction "1_1") (pintype "input"))
      (node (ref "R41") (pin "2") (pinfunction "2_2") (pintype "input"))
    )
    (net (code "48") (name "INVERTER_VOLT") (class "Default")
      (node (ref "CN11") (pin "3") (pinfunction "3_3") (pintype "unspecified"))
      (node (ref "R14") (pin "2") (pinfunction "2_2") (pintype "input"))
      (node (ref "电压比较器1") (pin "11") (pinfunction "IN+_11") (pintype "input"))
      (node (ref "电压比较器1") (pin "5") (pinfunction "IN+_5") (pintype "input"))
      (node (ref "电压比较器1") (pin "6") (pinfunction "IN-_6") (pintype "input"))
    )
    (net (code "49") (name "INVERTER_VOLT_REF") (class "Default")
      (node (ref "可调电阻2") (pin "2") (pinfunction "2_2") (pintype "unspecified"))
      (node (ref "电压比较器1") (pin "4") (pinfunction "IN-_4") (pintype "input"))
    )
    (net (code "50") (name "LOW_BATT+") (class "Default")
      (node (ref "CN7") (pin "1") (pinfunction "1_1") (pintype "unspecified"))
      (node (ref "FH1") (pin "2") (pinfunction "2_2") (pintype "unspecified"))
    )
    (net (code "51") (name "Net-(BACK-K)") (class "Default")
      (node (ref "BACK") (pin "2") (pinfunction "K_2") (pintype "unspecified"))
      (node (ref "R9") (pin "2") (pinfunction "2_2") (pintype "input"))
    )
    (net (code "52") (name "Net-(BATT-K)") (class "Default")
      (node (ref "BATT") (pin "2") (pinfunction "K_2") (pintype "unspecified"))
      (node (ref "R5") (pin "2") (pinfunction "2_2") (pintype "input"))
    )
    (net (code "53") (name "Net-(BMS-K)") (class "Default")
      (node (ref "BMS") (pin "2") (pinfunction "K_2") (pintype "unspecified"))
      (node (ref "R21") (pin "2") (pinfunction "2_2") (pintype "input"))
    )
    (net (code "54") (name "Net-(BSPD-K)") (class "Default")
      (node (ref "BSPD") (pin "2") (pinfunction "K_2") (pintype "unspecified"))
      (node (ref "R22") (pin "2") (pinfunction "2_2") (pintype "input"))
    )
    (net (code "55") (name "Net-(D1-A)") (class "Default")
      (node (ref "D1") (pin "2") (pinfunction "A_2") (pintype "unspecified"))
      (node (ref "NMOS1") (pin "3") (pinfunction "D_3") (pintype "unspecified"))
      (node (ref "继电器1") (pin "8") (pinfunction "8_8") (pintype "unspecified"))
    )
    (net (code "56") (name "Net-(D2-A)") (class "Default")
      (node (ref "D2") (pin "2") (pinfunction "A_2") (pintype "unspecified"))
      (node (ref "NMOS2") (pin "3") (pinfunction "D_3") (pintype "unspecified"))
      (node (ref "继电器2") (pin "8") (pinfunction "8_8") (pintype "unspecified"))
    )
    (net (code "57") (name "Net-(D3-A)") (class "Default")
      (node (ref "C7") (pin "2") (pinfunction "2_2") (pintype "unspecified"))
      (node (ref "D3") (pin "2") (pinfunction "A_2") (pintype "unspecified"))
      (node (ref "R29") (pin "1") (pinfunction "1_1") (pintype "input"))
      (node (ref "电压比较器5") (pin "11") (pinfunction "IN+_11") (pintype "input"))
    )
    (net (code "58") (name "Net-(D3-C)") (class "Default")
      (node (ref "D3") (pin "1") (pinfunction "C_1") (pintype "unspecified"))
      (node (ref "R24") (pin "1") (pinfunction "1_1") (pintype "input"))
    )
    (net (code "59") (name "Net-(FRONT-K)") (class "Default")
      (node (ref "FRONT") (pin "2") (pinfunction "K_2") (pintype "unspecified"))
      (node (ref "R16") (pin "2") (pinfunction "2_2") (pintype "input"))
    )
    (net (code "60") (name "Net-(HV-K)") (class "Default")
      (node (ref "HV") (pin "2") (pinfunction "K_2") (pintype "unspecified"))
      (node (ref "R13") (pin "2") (pinfunction "2_2") (pintype "input"))
    )
    (net (code "61") (name "Net-(IMD-K)") (class "Default")
      (node (ref "IMD") (pin "2") (pinfunction "K_2") (pintype "unspecified"))
      (node (ref "R20") (pin "2") (pinfunction "2_2") (pintype "input"))
    )
    (net (code "62") (name "Net-(LED1-+)") (class "Default")
      (node (ref "LED1") (pin "1") (pinfunction "+_1") (pintype "unspecified"))
      (node (ref "R4") (pin "1") (pinfunction "1_1") (pintype "input"))
    )
    (net (code "63") (name "Net-(LED2-+)") (class "Default")
      (node (ref "LED2") (pin "1") (pinfunction "+_1") (pintype "unspecified"))
      (node (ref "R8") (pin "1") (pinfunction "1_1") (pintype "input"))
    )
    (net (code "64") (name "Net-(NMOS1-G)") (class "Default")
      (node (ref "NMOS1") (pin "1") (pinfunction "G_1") (pintype "unspecified"))
      (node (ref "R32") (pin "1") (pinfunction "1_1") (pintype "input"))
      (node (ref "电压比较器6") (pin "2") (pinfunction "OUT_2") (pintype "unspecified"))
    )
    (net (code "65") (name "Net-(NMOS2-G)") (class "Default")
      (node (ref "NMOS2") (pin "1") (pinfunction "G_1") (pintype "unspecified"))
      (node (ref "R30") (pin "1") (pinfunction "1_1") (pintype "input"))
      (node (ref "电压比较器6") (pin "1") (pinfunction "OUT_1") (pintype "unspecified"))
    )
    (net (code "66") (name "Net-(NMOS3-G)") (class "Default")
      (node (ref "NMOS3") (pin "1") (pinfunction "G_1") (pintype "unspecified"))
      (node (ref "R25") (pin "2") (pinfunction "2_2") (pintype "input"))
      (node (ref "R26") (pin "1") (pinfunction "1_1") (pintype "input"))
    )
    (net (code "67") (name "Net-(NMOS4-G)") (class "Default")
      (node (ref "NMOS4") (pin "1") (pinfunction "G_1") (pintype "unspecified"))
      (node (ref "R43") (pin "1") (pinfunction "1_1") (pintype "input"))
      (node (ref "电压比较器2") (pin "13") (pinfunction "OUT_13") (pintype "unspecified"))
    )
    (net (code "68") (name "Net-(NMOS6-D)") (class "Default")
      (node (ref "NMOS6") (pin "3") (pinfunction "D_3") (pintype "unspecified"))
      (node (ref "R50") (pin "1") (pinfunction "1_1") (pintype "input"))
    )
    (net (code "69") (name "Net-(NMOS6-G)") (class "Default")
      (node (ref "NMOS6") (pin "1") (pinfunction "G_1") (pintype "unspecified"))
      (node (ref "R51") (pin "2") (pinfunction "2_2") (pintype "input"))
      (node (ref "R53") (pin "1") (pinfunction "1_1") (pintype "input"))
    )
    (net (code "70") (name "Net-(NMOS8-G)") (class "Default")
      (node (ref "NMOS8") (pin "1") (pinfunction "G_1") (pintype "unspecified"))
      (node (ref "R19") (pin "1") (pinfunction "1_1") (pintype "input"))
      (node (ref "电压比较器2") (pin "1") (pinfunction "OUT_1") (pintype "unspecified"))
      (node (ref "电压比较器2") (pin "2") (pinfunction "OUT_2") (pintype "unspecified"))
    )
    (net (code "71") (name "Net-(PMOS8-G)") (class "Default")
      (node (ref "PMOS8") (pin "1") (pinfunction "G_1") (pintype "unspecified"))
      (node (ref "R49") (pin "1") (pinfunction "1_1") (pintype "input"))
      (node (ref "R50") (pin "2") (pinfunction "2_2") (pintype "input"))
    )
    (net (code "72") (name "Net-(Q1-G)") (class "Default")
      (node (ref "Q1") (pin "1") (pinfunction "G_1") (pintype "unspecified"))
      (node (ref "R91") (pin "2") (pinfunction "2_2") (pintype "input"))
      (node (ref "R92") (pin "1") (pinfunction "1_1") (pintype "input"))
    )
    (net (code "73") (name "Net-(Q2-G)") (class "Default")
      (node (ref "Q2") (pin "1") (pinfunction "G_1") (pintype "unspecified"))
      (node (ref "R93") (pin "2") (pinfunction "2_2") (pintype "input"))
      (node (ref "R94") (pin "1") (pinfunction "1_1") (pintype "input"))
    )
    (net (code "74") (name "Net-(R82-Pad1)") (class "Default")
      (node (ref "R82") (pin "1") (pinfunction "1_1") (pintype "input"))
      (node (ref "R83") (pin "2") (pinfunction "2_2") (pintype "input"))
      (node (ref "U2") (pin "10") (pinfunction "Trim_10") (pintype "input"))
      (node (ref "U2") (pin "9") (pinfunction "Trim_9") (pintype "input"))
    )
    (net (code "75") (name "Net-(R112-Pad1)") (class "Default")
      (node (ref "R112") (pin "1") (pinfunction "1_1") (pintype "input"))
      (node (ref "R113") (pin "2") (pinfunction "2_2") (pintype "input"))
    )
    (net (code "76") (name "Net-(RING-K)") (class "Default")
      (node (ref "R17") (pin "2") (pinfunction "2_2") (pintype "input"))
      (node (ref "RING") (pin "2") (pinfunction "K_2") (pintype "unspecified"))
    )
    (net (code "77") (name "Net-(SIDE-K)") (class "Default")
      (node (ref "R10") (pin "2") (pinfunction "2_2") (pintype "input"))
      (node (ref "SIDE") (pin "2") (pinfunction "K_2") (pintype "unspecified"))
    )
    (net (code "78") (name "Net-(SW2-Pad2)") (class "Default")
      (node (ref "SW2") (pin "2") (pinfunction "2_2") (pintype "unspecified"))
      (node (ref "U2") (pin "3") (pinfunction "Crtl_3") (pintype "input"))
      (node (ref "U2") (pin "4") (pinfunction "Crtl_4") (pintype "input"))
    )
    (net (code "79") (name "Net-(SWLB+-K)") (class "Default")
      (node (ref "R112") (pin "2") (pinfunction "2_2") (pintype "input"))
      (node (ref "SWLB+") (pin "2") (pinfunction "K_2") (pintype "unspecified"))
    )
    (net (code "80") (name "Net-(TSALGREEN-K)") (class "Default")
      (node (ref "R96") (pin "2") (pinfunction "2_2") (pintype "input"))
      (node (ref "TSALGREEN") (pin "2") (pinfunction "K_2") (pintype "unspecified"))
    )
    (net (code "81") (name "Net-(TSALRED--)") (class "Default")
      (node (ref "R95") (pin "2") (pinfunction "2_2") (pintype "input"))
      (node (ref "TSALRED") (pin "2") (pinfunction "-_2") (pintype "unspecified"))
    )
    (net (code "82") (name "Net-(U1-CONT)") (class "Default")
      (node (ref "C5") (pin "2") (pinfunction "2_2") (pintype "input"))
      (node (ref "U1") (pin "5") (pinfunction "CONT_5") (pintype "unspecified"))
    )
    (net (code "83") (name "Net-(U1-DISCH)") (class "Default")
      (node (ref "R11") (pin "1") (pinfunction "1_1") (pintype "input"))
      (node (ref "R12") (pin "2") (pinfunction "2_2") (pintype "input"))
      (node (ref "U1") (pin "7") (pinfunction "DISCH_7") (pintype "unspecified"))
    )
    (net (code "84") (name "Net-(U1-THRES)") (class "Default")
      (node (ref "C6") (pin "2") (pinfunction "2_2") (pintype "unspecified"))
      (node (ref "R12") (pin "1") (pinfunction "1_1") (pintype "input"))
      (node (ref "U1") (pin "2") (pinfunction "TRIG_2") (pintype "unspecified"))
      (node (ref "U1") (pin "6") (pinfunction "THRES_6") (pintype "unspecified"))
    )
    (net (code "85") (name "Net-(U3-Y0#)") (class "Default")
      (node (ref "R110") (pin "1") (pinfunction "1_1") (pintype "unspecified"))
      (node (ref "U3") (pin "9") (pinfunction "Y0#_9") (pintype "unspecified"))
    )
    (net (code "86") (name "Net-(U3-Y1#)") (class "Default")
      (node (ref "R109") (pin "1") (pinfunction "1_1") (pintype "unspecified"))
      (node (ref "U3") (pin "7") (pinfunction "Y1#_7") (pintype "unspecified"))
    )
    (net (code "87") (name "Net-(U3-Y2#)") (class "Default")
      (node (ref "R108") (pin "1") (pinfunction "1_1") (pintype "input"))
      (node (ref "U3") (pin "6") (pinfunction "Y2#_6") (pintype "unspecified"))
    )
    (net (code "88") (name "Net-(U3-Y3#)") (class "Default")
      (node (ref "R107") (pin "2") (pinfunction "2_2") (pintype "input"))
      (node (ref "U3") (pin "14") (pinfunction "Y3#_14") (pintype "unspecified"))
    )
    (net (code "89") (name "Net-(电压比较器3A-IN+)") (class "Default")
      (node (ref "C8") (pin "1") (pinfunction "1_1") (pintype "unspecified"))
      (node (ref "R62") (pin "2") (pinfunction "2_2") (pintype "input"))
      (node (ref "电压比较器3") (pin "9") (pinfunction "IN+_9") (pintype "input"))
    )
    (net (code "90") (name "Net-(电压比较器5B-OUT)") (class "Default")
      (node (ref "R25") (pin "1") (pinfunction "1_1") (pintype "input"))
      (node (ref "R35") (pin "1") (pinfunction "1_1") (pintype "input"))
      (node (ref "电压比较器5") (pin "1") (pinfunction "OUT_1") (pintype "unspecified"))
    )
    (net (code "91") (name "Net-(电压比较器5D-OUT)") (class "Default")
      (node (ref "R26") (pin "2") (pinfunction "2_2") (pintype "input"))
      (node (ref "R36") (pin "1") (pinfunction "1_1") (pintype "input"))
      (node (ref "电压比较器5") (pin "2") (pinfunction "OUT_2") (pintype "unspecified"))
    )
    (net (code "92") (name "Net-(软起动PMOS1-G)") (class "Default")
      (node (ref "C1") (pin "1") (pinfunction "1_1") (pintype "unspecified"))
      (node (ref "R6") (pin "1") (pinfunction "1_1") (pintype "input"))
      (node (ref "R7") (pin "2") (pinfunction "2_2") (pintype "input"))
      (node (ref "软起动PMOS1") (pin "1") (pinfunction "G_1") (pintype "unspecified"))
    )
    (net (code "93") (name "PUMP_ENABLE") (class "Default")
      (node (ref "CN10") (pin "9") (pinfunction "9_9") (pintype "unspecified"))
      (node (ref "R92") (pin "2") (pinfunction "2_2") (pintype "input"))
    )
    (net (code "94") (name "PUMP_PWM-") (class "Default")
      (node (ref "CN1") (pin "17") (pinfunction "17_17") (pintype "unspecified"))
      (node (ref "CN2") (pin "9") (pinfunction "9_9") (pintype "unspecified"))
      (node (ref "D4") (pin "2") (pinfunction "A_2") (pintype "unspecified"))
      (node (ref "Q1") (pin "4") (pinfunction "D_4") (pintype "unspecified"))
    )
    (net (code "95") (name "REDLIGHT_ON") (class "Default")
      (node (ref "R15") (pin "1") (pinfunction "1_1") (pintype "input"))
      (node (ref "电压比较器1") (pin "2") (pinfunction "OUT_2") (pintype "unspecified"))
      (node (ref "电压比较器2") (pin "5") (pinfunction "IN+_5") (pintype "input"))
    )
    (net (code "96") (name "RED_SCS_NORMAL") (class "Default")
      (node (ref "R18") (pin "1") (pinfunction "1_1") (pintype "input"))
      (node (ref "电压比较器1") (pin "1") (pinfunction "OUT_1") (pintype "unspecified"))
      (node (ref "电压比较器1") (pin "13") (pinfunction "OUT_13") (pintype "unspecified"))
      (node (ref "电压比较器2") (pin "7") (pinfunction "IN+_7") (pintype "input"))
    )
    (net (code "97") (name "SC_02") (class "Default")
      (node (ref "BSPD") (pin "1") (pinfunction "A_1") (pintype "unspecified"))
      (node (ref "CN9") (pin "4") (pinfunction "4_4") (pintype "unspecified"))
      (node (ref "继电器1") (pin "6") (pinfunction "6_6") (pintype "unspecified"))
    )
    (net (code "98") (name "SC_02_4V") (class "Default")
      (node (ref "R22") (pin "1") (pinfunction "1_1") (pintype "input"))
      (node (ref "R97") (pin "2") (pinfunction "2_2") (pintype "input"))
      (node (ref "U3") (pin "10") (pinfunction "A8#_10") (pintype "unspecified"))
    )
    (net (code "99") (name "SC_03") (class "Default")
      (node (ref "BMS") (pin "1") (pinfunction "A_1") (pintype "unspecified"))
      (node (ref "继电器1") (pin "5") (pinfunction "5_5") (pintype "unspecified"))
      (node (ref "继电器2") (pin "6") (pinfunction "6_6") (pintype "unspecified"))
    )
    (net (code "100") (name "SC_03_4V") (class "Default")
      (node (ref "R21") (pin "1") (pinfunction "1_1") (pintype "input"))
      (node (ref "R98") (pin "2") (pinfunction "2_2") (pintype "input"))
      (node (ref "U3") (pin "5") (pinfunction "A7#_5") (pintype "unspecified"))
    )
    (net (code "101") (name "SC_04") (class "Default")
      (node (ref "CN4") (pin "4") (pinfunction "4_4") (pintype "unspecified"))
      (node (ref "IMD") (pin "1") (pinfunction "A_1") (pintype "unspecified"))
      (node (ref "继电器2") (pin "5") (pinfunction "5_5") (pintype "unspecified"))
    )
    (net (code "102") (name "SC_04_4V") (class "Default")
      (node (ref "R20") (pin "1") (pinfunction "1_1") (pintype "input"))
      (node (ref "R99") (pin "2") (pinfunction "2_2") (pintype "input"))
      (node (ref "U3") (pin "4") (pinfunction "A6#_4") (pintype "unspecified"))
    )
    (net (code "103") (name "SC_05") (class "Default")
      (node (ref "CN1") (pin "9") (pinfunction "9_9") (pintype "unspecified"))
      (node (ref "CN4") (pin "5") (pinfunction "5_5") (pintype "unspecified"))
      (node (ref "RING") (pin "1") (pinfunction "A_1") (pintype "unspecified"))
    )
    (net (code "104") (name "SC_05_4V") (class "Default")
      (node (ref "R100") (pin "2") (pinfunction "2_2") (pintype "input"))
      (node (ref "R17") (pin "1") (pinfunction "1_1") (pintype "input"))
      (node (ref "U3") (pin "3") (pinfunction "A5#_3") (pintype "unspecified"))
    )
    (net (code "105") (name "SC_06") (class "Default")
      (node (ref "CN1") (pin "10") (pinfunction "10_10") (pintype "unspecified"))
      (node (ref "CN11") (pin "8") (pinfunction "8_8") (pintype "unspecified"))
      (node (ref "FRONT") (pin "1") (pinfunction "A_1") (pintype "unspecified"))
    )
    (net (code "106") (name "SC_06_4V") (class "Default")
      (node (ref "R101") (pin "2") (pinfunction "2_2") (pintype "input"))
      (node (ref "R16") (pin "1") (pinfunction "1_1") (pintype "input"))
      (node (ref "U3") (pin "2") (pinfunction "A4#_2") (pintype "unspecified"))
    )
    (net (code "107") (name "SC_07") (class "Default")
      (node (ref "CN11") (pin "9") (pinfunction "9_9") (pintype "unspecified"))
      (node (ref "CN5") (pin "4") (pinfunction "4_4") (pintype "unspecified"))
      (node (ref "HV") (pin "1") (pinfunction "A_1") (pintype "unspecified"))
    )
    (net (code "108") (name "SC_07_4V") (class "Default")
      (node (ref "R102") (pin "2") (pinfunction "2_2") (pintype "input"))
      (node (ref "R13") (pin "1") (pinfunction "1_1") (pintype "input"))
      (node (ref "U3") (pin "1") (pinfunction "A3#_1") (pintype "unspecified"))
    )
    (net (code "109") (name "SC_08") (class "Default")
      (node (ref "CN2") (pin "6") (pinfunction "6_6") (pintype "unspecified"))
      (node (ref "CN5") (pin "5") (pinfunction "5_5") (pintype "unspecified"))
      (node (ref "SIDE") (pin "1") (pinfunction "A_1") (pintype "unspecified"))
    )
    (net (code "110") (name "SC_08_4V") (class "Default")
      (node (ref "R10") (pin "1") (pinfunction "1_1") (pintype "input"))
      (node (ref "R103") (pin "2") (pinfunction "2_2") (pintype "input"))
      (node (ref "U3") (pin "13") (pinfunction "A2#_13") (pintype "unspecified"))
    )
    (net (code "111") (name "SC_09") (class "Default")
      (node (ref "BACK") (pin "1") (pinfunction "A_1") (pintype "unspecified"))
      (node (ref "CN2") (pin "7") (pinfunction "7_7") (pintype "unspecified"))
      (node (ref "CN6") (pin "8") (pinfunction "8_8") (pintype "unspecified"))
    )
    (net (code "112") (name "SC_09_4V") (class "Default")
      (node (ref "R104") (pin "2") (pinfunction "2_2") (pintype "input"))
      (node (ref "R9") (pin "1") (pinfunction "1_1") (pintype "input"))
      (node (ref "U3") (pin "12") (pinfunction "A1#_12") (pintype "unspecified"))
    )
    (net (code "113") (name "SC_10") (class "Default")
      (node (ref "BATT") (pin "1") (pinfunction "A_1") (pintype "unspecified"))
      (node (ref "CN10") (pin "7") (pinfunction "7_7") (pintype "unspecified"))
      (node (ref "CN11") (pin "4") (pinfunction "4_4") (pintype "unspecified"))
      (node (ref "CN6") (pin "10") (pinfunction "10_10") (pintype "unspecified"))
      (node (ref "CN6") (pin "9") (pinfunction "9_9") (pintype "unspecified"))
    )
    (net (code "114") (name "SC_10_4V") (class "Default")
      (node (ref "R105") (pin "2") (pinfunction "2_2") (pintype "input"))
      (node (ref "R5") (pin "1") (pinfunction "1_1") (pintype "input"))
      (node (ref "U3") (pin "11") (pinfunction "A0#_11") (pintype "unspecified"))
    )
    (net (code "115") (name "SC_STATUS") (class "Default")
      (node (ref "CN10") (pin "21") (pinfunction "21_21") (pintype "unspecified"))
      (node (ref "R107") (pin "1") (pinfunction "1_1") (pintype "input"))
      (node (ref "R108") (pin "2") (pinfunction "2_2") (pintype "input"))
      (node (ref "R109") (pin "2") (pinfunction "2_2") (pintype "unspecified"))
      (node (ref "R110") (pin "2") (pinfunction "2_2") (pintype "unspecified"))
      (node (ref "R111") (pin "2") (pinfunction "2_2") (pintype "input"))
    )
    (net (code "116") (name "SOFTED_LOW_BATT+") (class "Default")
      (node (ref "C2") (pin "2") (pinfunction "2_2") (pintype "unspecified"))
      (node (ref "C3") (pin "1") (pinfunction "1_1") (pintype "input"))
      (node (ref "D4") (pin "1") (pinfunction "C_1") (pintype "unspecified"))
      (node (ref "D5") (pin "1") (pinfunction "C_1") (pintype "unspecified"))
      (node (ref "DC/DC1") (pin "1") (pinfunction "Vin_1") (pintype "unspecified"))
      (node (ref "U2") (pin "1") (pinfunction "+Vin_1") (pintype "input"))
      (node (ref "U2") (pin "2") (pinfunction "+Vin_2") (pintype "input"))
      (node (ref "软起动PMOS1") (pin "2") (pinfunction "D_2") (pintype "unspecified"))
    )
    (net (code "117") (name "STEERING_ANGLE") (class "Default")
      (node (ref "CN1") (pin "21") (pinfunction "21_21") (pintype "unspecified"))
      (node (ref "CN10") (pin "22") (pinfunction "22_22") (pintype "unspecified"))
    )
    (net (code "118") (name "SWED_LOW_BATT+") (class "Default")
      (node (ref "C1") (pin "2") (pinfunction "2_2") (pintype "unspecified"))
      (node (ref "CN1") (pin "16") (pinfunction "16_16") (pintype "unspecified"))
      (node (ref "CN1") (pin "18") (pinfunction "18_18") (pintype "unspecified"))
      (node (ref "CN10") (pin "1") (pinfunction "1_1") (pintype "unspecified"))
      (node (ref "CN10") (pin "2") (pinfunction "2_2") (pintype "unspecified"))
      (node (ref "CN10") (pin "3") (pinfunction "3_3") (pintype "unspecified"))
      (node (ref "CN2") (pin "10") (pinfunction "10_10") (pintype "unspecified"))
      (node (ref "CN2") (pin "8") (pinfunction "8_8") (pintype "unspecified"))
      (node (ref "CN5") (pin "10") (pinfunction "10_10") (pintype "unspecified"))
      (node (ref "CN9") (pin "1") (pinfunction "1_1") (pintype "unspecified"))
      (node (ref "CN9") (pin "3") (pinfunction "3_3") (pintype "unspecified"))
      (node (ref "R6") (pin "2") (pinfunction "2_2") (pintype "input"))
      (node (ref "SWLB+") (pin "1") (pinfunction "A_1") (pintype "unspecified"))
      (node (ref "软起动PMOS1") (pin "3") (pinfunction "S_3") (pintype "unspecified"))
    )
    (net (code "119") (name "TSAL_GREEN-") (class "Default")
      (node (ref "CN4") (pin "2") (pinfunction "2_2") (pintype "unspecified"))
      (node (ref "NMOS7") (pin "3") (pinfunction "D_3") (pintype "unspecified"))
      (node (ref "R96") (pin "1") (pinfunction "1_1") (pintype "input"))
    )
    (net (code "120") (name "TSAL_RED-") (class "Default")
      (node (ref "CN4") (pin "3") (pinfunction "3_3") (pintype "unspecified"))
      (node (ref "NMOS8") (pin "3") (pinfunction "D_3") (pintype "unspecified"))
      (node (ref "R95") (pin "1") (pinfunction "1_1") (pintype "input"))
    )
    (net (code "121") (name "TS_OFF-") (class "Default")
      (node (ref "CN1") (pin "8") (pinfunction "8_8") (pintype "unspecified"))
      (node (ref "NMOS3") (pin "3") (pinfunction "D_3") (pintype "unspecified"))
    )
    (net (code "122") (name "TS_OFF_ON") (class "Default")
      (node (ref "NMOS7") (pin "1") (pinfunction "G_1") (pintype "unspecified"))
      (node (ref "R76") (pin "1") (pinfunction "1_1") (pintype "input"))
      (node (ref "电压比较器4") (pin "13") (pinfunction "OUT_13") (pintype "unspecified"))
      (node (ref "电压比较器4") (pin "14") (pinfunction "OUT_14") (pintype "unspecified"))
      (node (ref "电压比较器5") (pin "5") (pinfunction "IN+_5") (pintype "input"))
    )
    (net (code "123") (name "VISIBILITY_CHECK") (class "Default")
      (node (ref "PMOS2") (pin "1") (pinfunction "G_1") (pintype "unspecified"))
      (node (ref "PMOS3") (pin "1") (pinfunction "G_1") (pintype "unspecified"))
      (node (ref "PMOS4") (pin "1") (pinfunction "G_1") (pintype "unspecified"))
      (node (ref "PMOS5") (pin "1") (pinfunction "G_1") (pintype "unspecified"))
      (node (ref "R23") (pin "1") (pinfunction "1_1") (pintype "input"))
      (node (ref "电压比较器5") (pin "13") (pinfunction "OUT_13") (pintype "unspecified"))
      (node (ref "电压比较器5") (pin "6") (pinfunction "IN-_6") (pintype "input"))
    )
    (net (code "124") (name "unconnected-(CN1-Pad22)") (class "Default")
      (node (ref "CN1") (pin "22") (pinfunction "22_22") (pintype "unspecified+no_connect"))
    )
    (net (code "125") (name "unconnected-(CN2-Pad12)") (class "Default")
      (node (ref "CN2") (pin "12") (pinfunction "12_12") (pintype "unspecified"))
    )
    (net (code "126") (name "unconnected-(CN2-Pad13)") (class "Default")
      (node (ref "CN2") (pin "13") (pinfunction "13_13") (pintype "unspecified"))
    )
    (net (code "127") (name "unconnected-(CN2-Pad14)") (class "Default")
      (node (ref "CN2") (pin "14") (pinfunction "14_14") (pintype "unspecified"))
    )
    (net (code "128") (name "unconnected-(CN6-Pad11)") (class "Default")
      (node (ref "CN6") (pin "11") (pinfunction "11_11") (pintype "unspecified"))
    )
    (net (code "129") (name "unconnected-(SW2-Pad1)") (class "Default")
      (node (ref "SW2") (pin "1") (pinfunction "1_1") (pintype "unspecified+no_connect"))
    )
    (net (code "130") (name "unconnected-(U3-NC-Pad15)") (class "Default")
      (node (ref "U3") (pin "15") (pinfunction "NC_15") (pintype "unspecified+no_connect"))
    )
    (net (code "131") (name "unconnected-(继电器1-Pad7)") (class "Default")
      (node (ref "继电器1") (pin "7") (pinfunction "7_7") (pintype "unspecified+no_connect"))
    )
    (net (code "132") (name "unconnected-(继电器2-Pad7)") (class "Default")
      (node (ref "继电器2") (pin "7") (pinfunction "7_7") (pintype "unspecified+no_connect"))
    )
  )
)
